# KickerBoard-new-small.net
KiCad netlist of a schematic drawn in EAGLE
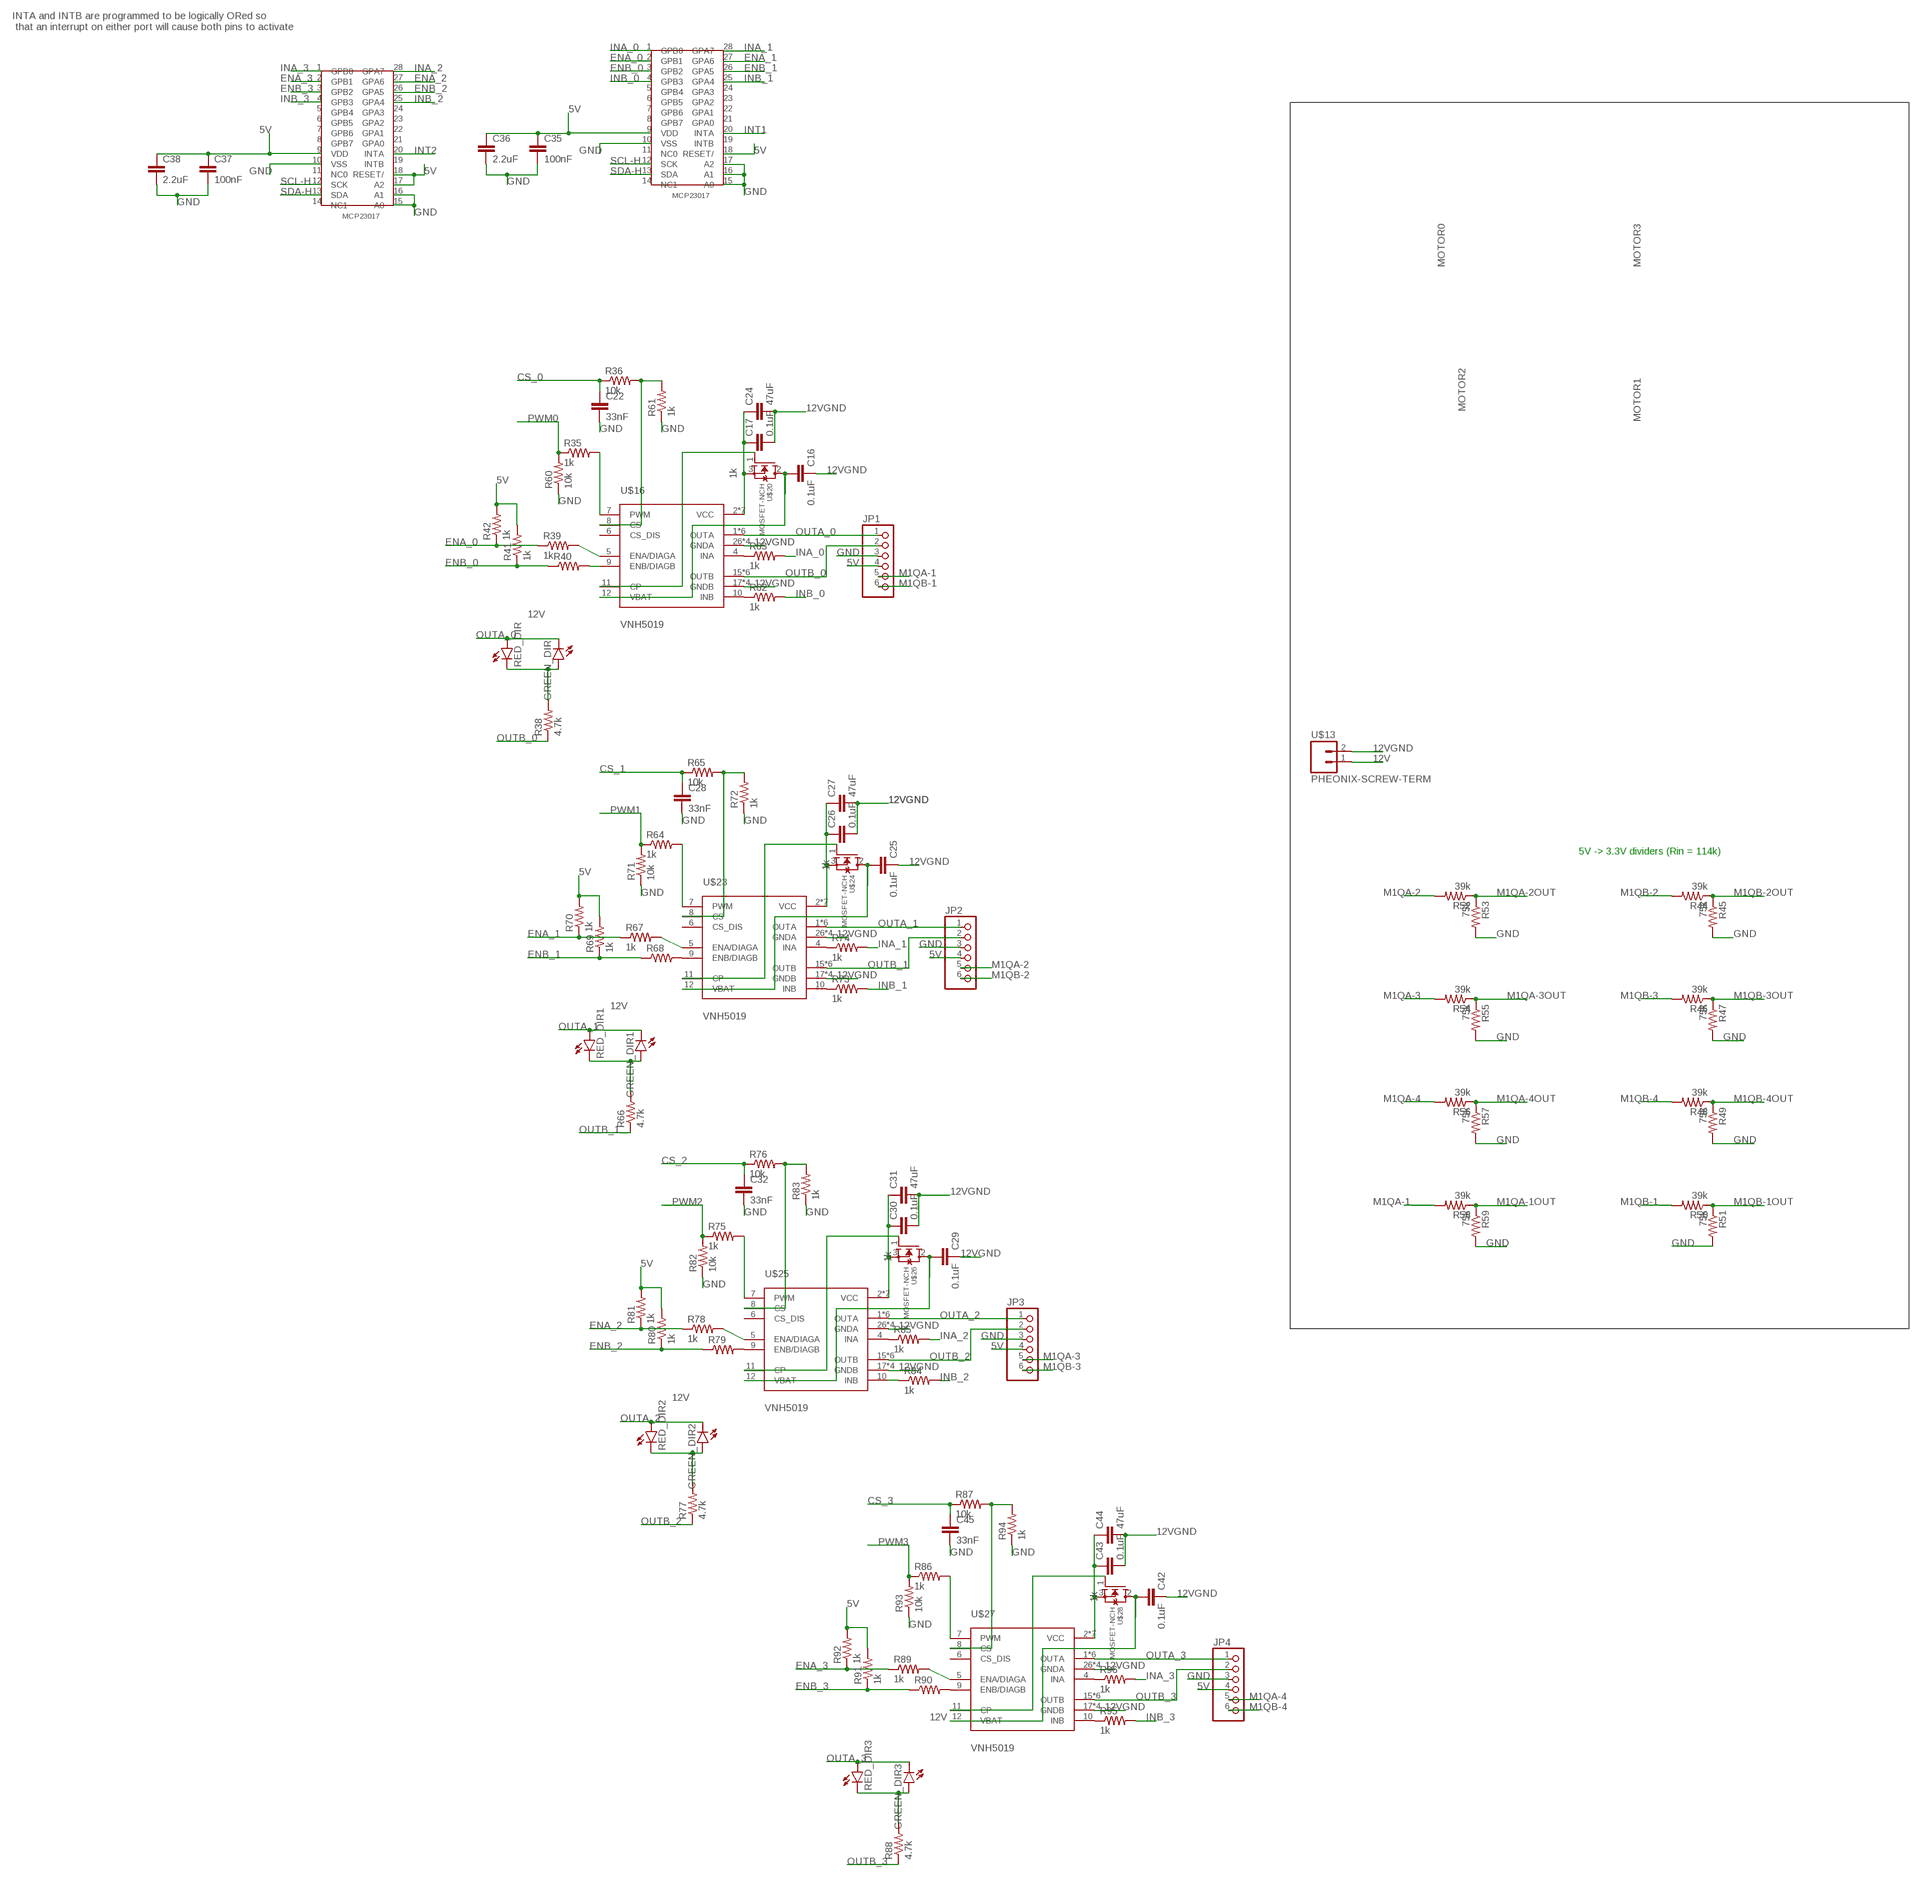
[diagram p0: schematic, sheet 1, part 1 of 2]
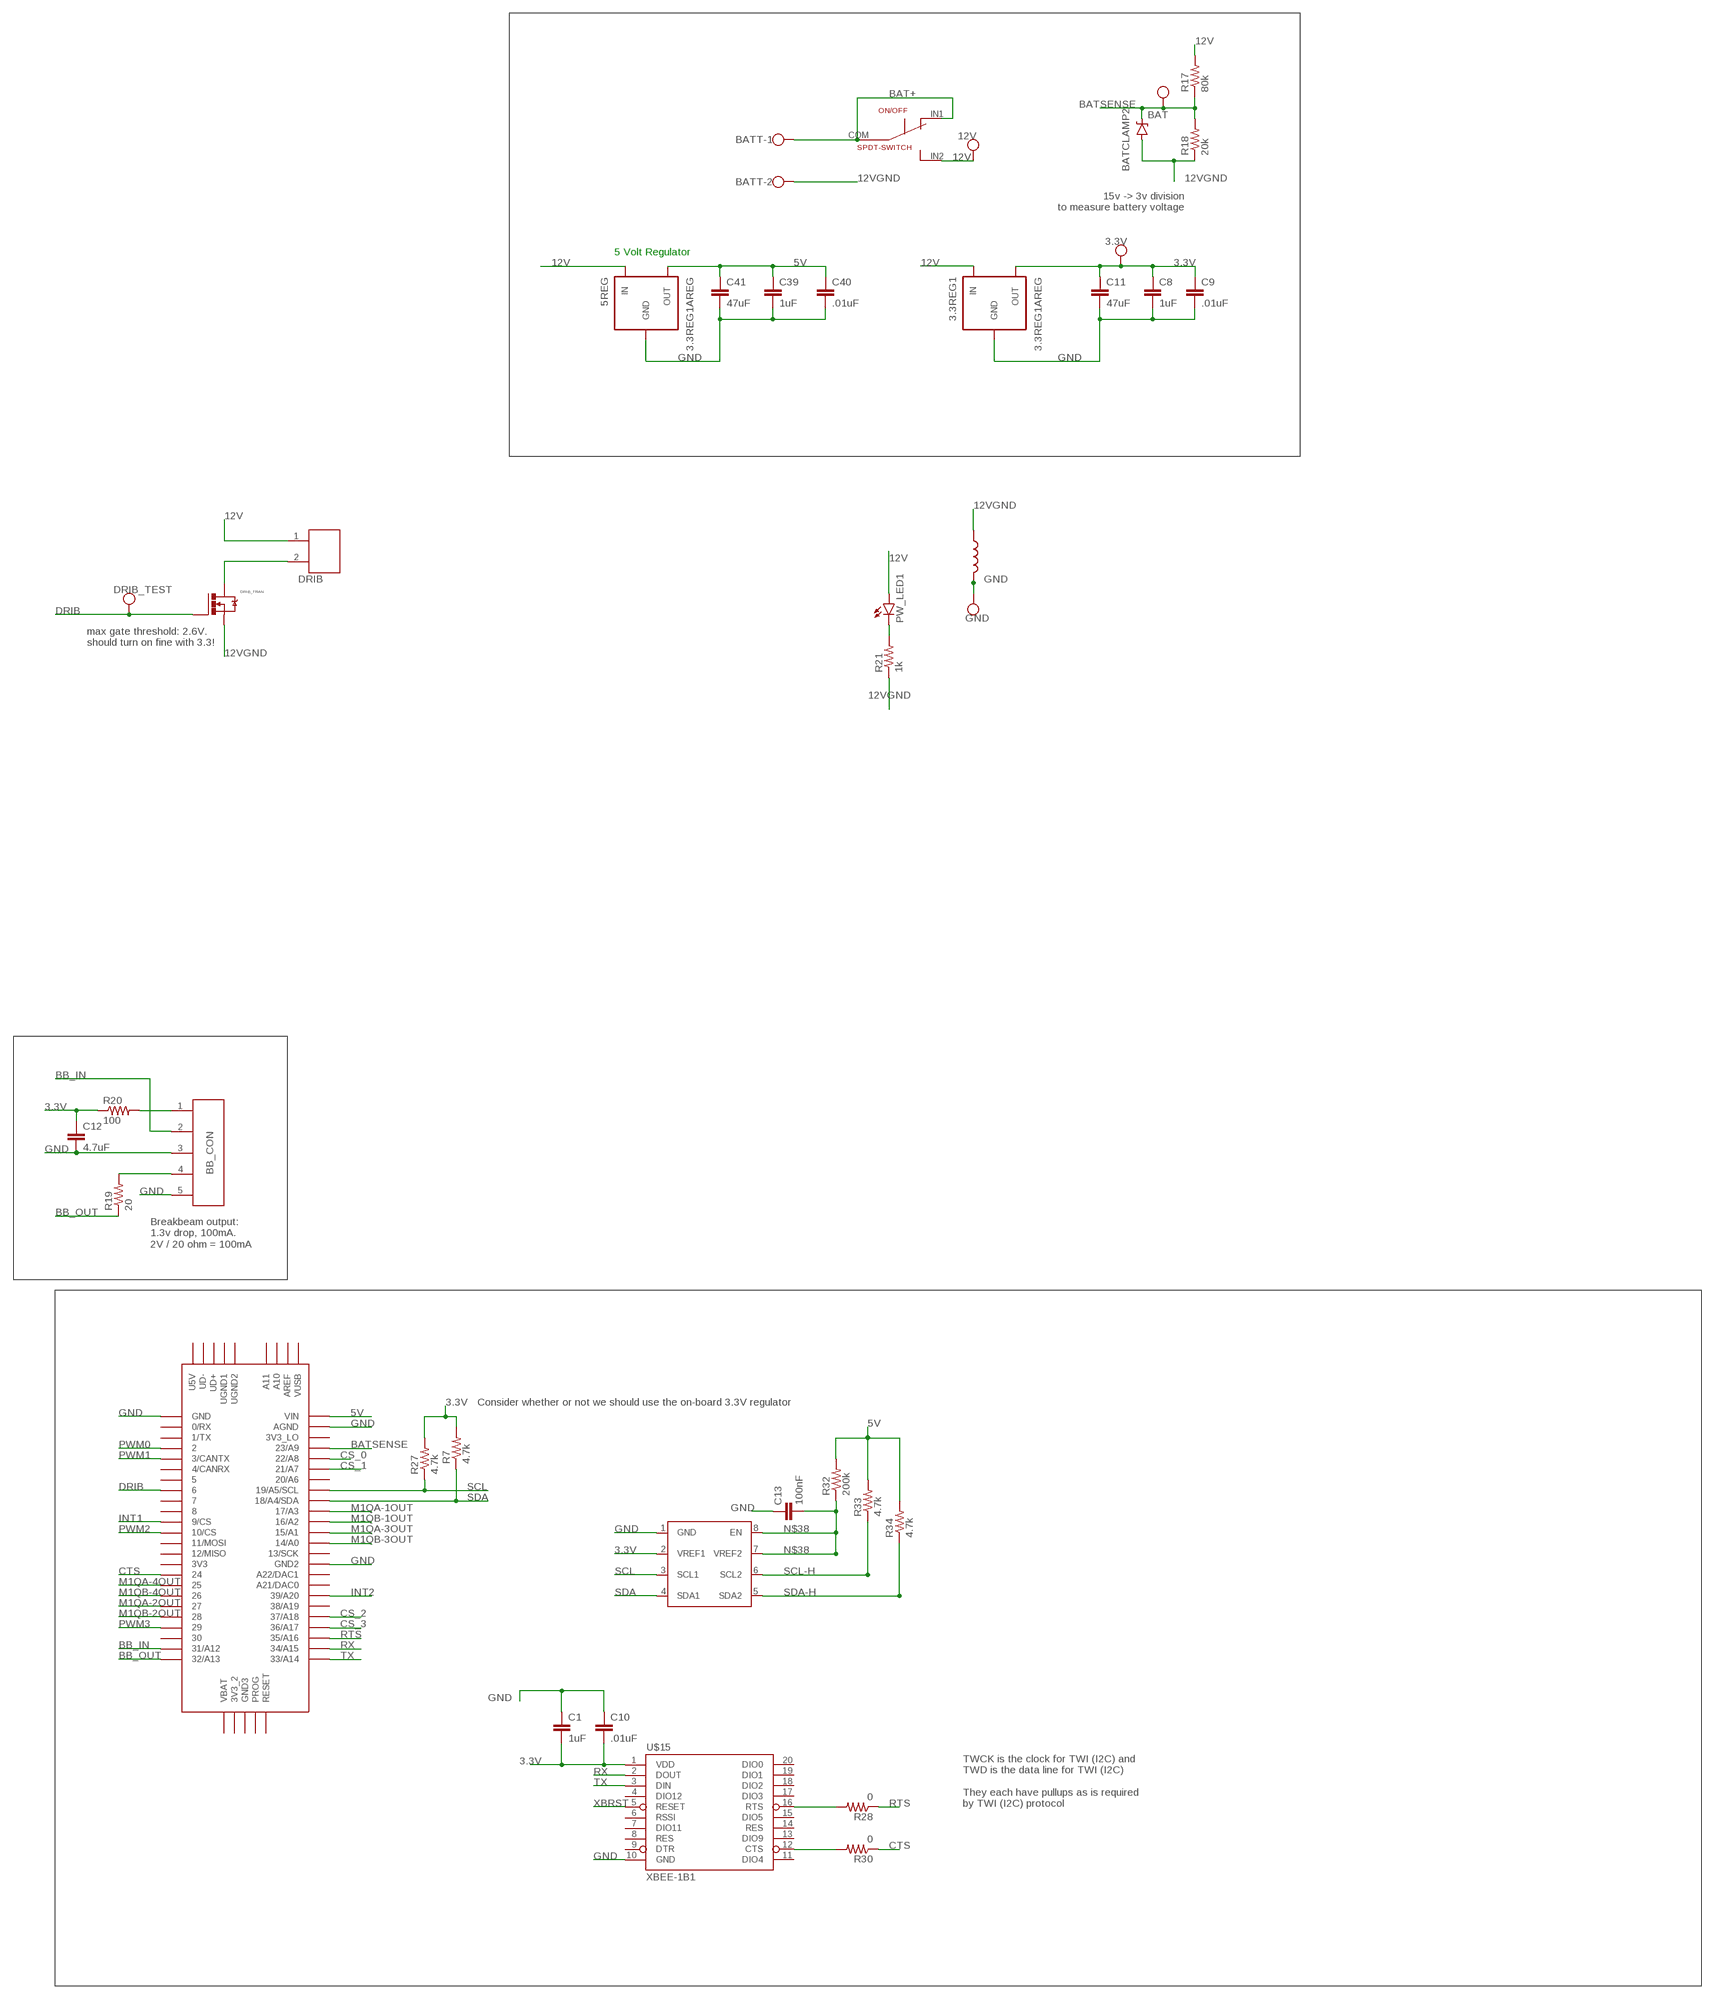
[diagram p1: schematic, sheet 1, part 2 of 2]

(export (version "E")
  (design (tool "Eeschema 10.0.6"))
  (components
    (comp (ref "3.3REG1")
      (value "3.3REG1AREG")
      (footprint "eagle-import:DPAK")
      (libsource (lib "eagle-import") (part "3.3REG1AREG"))
    )
    (comp (ref "3.3V")
      (value "TEST_PT")
      (footprint "eagle-import:TESTING_PT")
      (libsource (lib "eagle-import") (part "TEST_PT"))
    )
    (comp (ref "5REG")
      (value "3.3REG1AREG")
      (footprint "eagle-import:DPAK")
      (libsource (lib "eagle-import") (part "3.3REG1AREG"))
    )
    (comp (ref "12V")
      (value "TEST_PT")
      (footprint "eagle-import:TESTING_PT")
      (libsource (lib "eagle-import") (part "TEST_PT"))
    )
    (comp (ref "BAT")
      (value "TEST_PT")
      (footprint "eagle-import:TESTING_PT")
      (libsource (lib "eagle-import") (part "TEST_PT"))
    )
    (comp (ref "BATCLAMP2")
      (value "DIODE-ZENERDO214AC")
      (footprint "eagle-import:DO214AC")
      (libsource (lib "eagle-import") (part "DIODE-ZENERDO214AC"))
    )
    (comp (ref "BATT")
      (value "W237-102")
      (footprint "eagle-import:W237-102")
      (fields (field (name "MPN") "237-102"))
      (libsource (lib "eagle-import") (part "W237-102"))
    )
    (comp (ref "BB_CON")
      (value "JST-5")
      (footprint "eagle-import:JST-5-2MM")
      (libsource (lib "eagle-import") (part "JST-5"))
    )
    (comp (ref "C1")
      (value "1uF")
      (footprint "eagle-import:1206")
      (libsource (lib "eagle-import") (part "CAP1206"))
    )
    (comp (ref "C8")
      (value "1uF")
      (footprint "eagle-import:0805")
      (libsource (lib "eagle-import") (part "CAP0805"))
    )
    (comp (ref "C9")
      (value ".01uF")
      (footprint "eagle-import:0805")
      (libsource (lib "eagle-import") (part "CAP0805"))
    )
    (comp (ref "C10")
      (value ".01uF")
      (footprint "eagle-import:1206")
      (libsource (lib "eagle-import") (part "CAP1206"))
    )
    (comp (ref "C11")
      (value "47uF")
      (footprint "eagle-import:1206")
      (libsource (lib "eagle-import") (part "CAP1206"))
    )
    (comp (ref "C12")
      (value "4.7uF")
      (footprint "eagle-import:0805")
      (libsource (lib "eagle-import") (part "CAP0805"))
    )
    (comp (ref "C13")
      (value "100nF")
      (footprint "eagle-import:0805")
      (libsource (lib "eagle-import") (part "CAP0805"))
    )
    (comp (ref "C16")
      (value "0.1uF")
      (footprint "eagle-import:0805")
      (libsource (lib "eagle-import") (part "CAP0805"))
    )
    (comp (ref "C17")
      (value "0.1uF")
      (footprint "eagle-import:0805")
      (libsource (lib "eagle-import") (part "CAP0805"))
    )
    (comp (ref "C22")
      (value "33nF")
      (footprint "eagle-import:0805")
      (libsource (lib "eagle-import") (part "CAP0805"))
    )
    (comp (ref "C24")
      (value "47uF")
      (footprint "eagle-import:1206")
      (libsource (lib "eagle-import") (part "CAP1206"))
    )
    (comp (ref "C25")
      (value "0.1uF")
      (footprint "eagle-import:0805")
      (libsource (lib "eagle-import") (part "CAP0805"))
    )
    (comp (ref "C26")
      (value "0.1uF")
      (footprint "eagle-import:0805")
      (libsource (lib "eagle-import") (part "CAP0805"))
    )
    (comp (ref "C27")
      (value "47uF")
      (footprint "eagle-import:1206")
      (libsource (lib "eagle-import") (part "CAP1206"))
    )
    (comp (ref "C28")
      (value "33nF")
      (footprint "eagle-import:0805")
      (libsource (lib "eagle-import") (part "CAP0805"))
    )
    (comp (ref "C29")
      (value "0.1uF")
      (footprint "eagle-import:0805")
      (libsource (lib "eagle-import") (part "CAP0805"))
    )
    (comp (ref "C30")
      (value "0.1uF")
      (footprint "eagle-import:0805")
      (libsource (lib "eagle-import") (part "CAP0805"))
    )
    (comp (ref "C31")
      (value "47uF")
      (footprint "eagle-import:1206")
      (libsource (lib "eagle-import") (part "CAP1206"))
    )
    (comp (ref "C32")
      (value "33nF")
      (footprint "eagle-import:0805")
      (libsource (lib "eagle-import") (part "CAP0805"))
    )
    (comp (ref "C35")
      (value "100nF")
      (footprint "eagle-import:0805")
      (libsource (lib "eagle-import") (part "CAP0805"))
    )
    (comp (ref "C36")
      (value "2.2uF")
      (footprint "eagle-import:0805")
      (libsource (lib "eagle-import") (part "CAP0805"))
    )
    (comp (ref "C37")
      (value "100nF")
      (footprint "eagle-import:0805")
      (libsource (lib "eagle-import") (part "CAP0805"))
    )
    (comp (ref "C38")
      (value "2.2uF")
      (footprint "eagle-import:0805")
      (libsource (lib "eagle-import") (part "CAP0805"))
    )
    (comp (ref "C39")
      (value "1uF")
      (footprint "eagle-import:0805")
      (libsource (lib "eagle-import") (part "CAP0805"))
    )
    (comp (ref "C40")
      (value ".01uF")
      (footprint "eagle-import:0805")
      (libsource (lib "eagle-import") (part "CAP0805"))
    )
    (comp (ref "C41")
      (value "47uF")
      (footprint "eagle-import:1206")
      (libsource (lib "eagle-import") (part "CAP1206"))
    )
    (comp (ref "C42")
      (value "0.1uF")
      (footprint "eagle-import:0805")
      (libsource (lib "eagle-import") (part "CAP0805"))
    )
    (comp (ref "C43")
      (value "0.1uF")
      (footprint "eagle-import:0805")
      (libsource (lib "eagle-import") (part "CAP0805"))
    )
    (comp (ref "C44")
      (value "47uF")
      (footprint "eagle-import:1206")
      (libsource (lib "eagle-import") (part "CAP1206"))
    )
    (comp (ref "C45")
      (value "33nF")
      (footprint "eagle-import:0805")
      (libsource (lib "eagle-import") (part "CAP0805"))
    )
    (comp (ref "DRIB")
      (value "JST-22MM")
      (footprint "eagle-import:JST-2-2MM")
      (libsource (lib "eagle-import") (part "JST-22MM"))
    )
    (comp (ref "DRIB_TEST")
      (value "TEST_PT")
      (footprint "eagle-import:TESTING_PT")
      (libsource (lib "eagle-import") (part "TEST_PT"))
    )
    (comp (ref "DRIB_TRAN")
      (value "N-MOSFETDPAK")
      (footprint "eagle-import:DPAK")
      (libsource (lib "eagle-import") (part "N-MOSFETDPAK"))
    )
    (comp (ref "GND")
      (value "TEST_PT")
      (footprint "eagle-import:TESTING_PT")
      (libsource (lib "eagle-import") (part "TEST_PT"))
    )
    (comp (ref "GREEN_DIR")
      (value "LED1206")
      (footprint "eagle-import:LED-1206")
      (libsource (lib "eagle-import") (part "LED1206"))
    )
    (comp (ref "GREEN_DIR1")
      (value "LED1206")
      (footprint "eagle-import:LED-1206")
      (libsource (lib "eagle-import") (part "LED1206"))
    )
    (comp (ref "GREEN_DIR2")
      (value "LED1206")
      (footprint "eagle-import:LED-1206")
      (libsource (lib "eagle-import") (part "LED1206"))
    )
    (comp (ref "GREEN_DIR3")
      (value "LED1206")
      (footprint "eagle-import:LED-1206")
      (libsource (lib "eagle-import") (part "LED1206"))
    )
    (comp (ref "JP1")
      (value "PINHD-1X6")
      (footprint "eagle-import:1X06")
      (libsource (lib "eagle-import") (part "PINHD-1X6"))
    )
    (comp (ref "JP2")
      (value "PINHD-1X6")
      (footprint "eagle-import:1X06")
      (libsource (lib "eagle-import") (part "PINHD-1X6"))
    )
    (comp (ref "JP3")
      (value "PINHD-1X6")
      (footprint "eagle-import:1X06")
      (libsource (lib "eagle-import") (part "PINHD-1X6"))
    )
    (comp (ref "JP4")
      (value "PINHD-1X6")
      (footprint "eagle-import:1X06")
      (libsource (lib "eagle-import") (part "PINHD-1X6"))
    )
    (comp (ref "ON/OFF")
      (value "SPDT-SWITCH")
      (footprint "eagle-import:CK_SWITCH")
      (libsource (lib "eagle-import") (part "SPDT-SWITCH"))
    )
    (comp (ref "PW_LED1")
      (value "LED1206")
      (footprint "eagle-import:LED-1206")
      (libsource (lib "eagle-import") (part "LED1206"))
    )
    (comp (ref "R7")
      (value "4.7k")
      (footprint "eagle-import:0805")
      (libsource (lib "eagle-import") (part "SparkFun-Resistors_RESISTOR0805-RES"))
    )
    (comp (ref "R17")
      (value "80k")
      (footprint "eagle-import:0805")
      (libsource (lib "eagle-import") (part "RESISTOR0805-RES"))
    )
    (comp (ref "R18")
      (value "20k")
      (footprint "eagle-import:0805")
      (libsource (lib "eagle-import") (part "RESISTOR0805-RES"))
    )
    (comp (ref "R19")
      (value "20")
      (footprint "eagle-import:0805")
      (libsource (lib "eagle-import") (part "RESISTOR0805-RES"))
    )
    (comp (ref "R20")
      (value "100")
      (footprint "eagle-import:0805")
      (libsource (lib "eagle-import") (part "RESISTOR0805-RES"))
    )
    (comp (ref "R21")
      (value "1k")
      (footprint "eagle-import:0805")
      (libsource (lib "eagle-import") (part "RESISTOR0805-RES"))
    )
    (comp (ref "R27")
      (value "4.7k")
      (footprint "eagle-import:0805")
      (libsource (lib "eagle-import") (part "SparkFun-Resistors_RESISTOR0805-RES"))
    )
    (comp (ref "R28")
      (value "0")
      (footprint "eagle-import:0805")
      (libsource (lib "eagle-import") (part "SparkFun-Resistors_RESISTOR0805-RES"))
    )
    (comp (ref "R30")
      (value "0")
      (footprint "eagle-import:0805")
      (libsource (lib "eagle-import") (part "SparkFun-Resistors_RESISTOR0805-RES"))
    )
    (comp (ref "R32")
      (value "200k")
      (footprint "eagle-import:0805")
      (libsource (lib "eagle-import") (part "SparkFun-Resistors_RESISTOR0805-RES"))
    )
    (comp (ref "R33")
      (value "4.7k")
      (footprint "eagle-import:0805")
      (libsource (lib "eagle-import") (part "SparkFun-Resistors_RESISTOR0805-RES"))
    )
    (comp (ref "R34")
      (value "4.7k")
      (footprint "eagle-import:0805")
      (libsource (lib "eagle-import") (part "SparkFun-Resistors_RESISTOR0805-RES"))
    )
    (comp (ref "R35")
      (value "1k")
      (footprint "eagle-import:0805")
      (libsource (lib "eagle-import") (part "RESISTOR0805-RES"))
    )
    (comp (ref "R36")
      (value "10k")
      (footprint "eagle-import:0805")
      (libsource (lib "eagle-import") (part "RESISTOR0805-RES"))
    )
    (comp (ref "R38")
      (value "4.7k")
      (footprint "eagle-import:0805")
      (libsource (lib "eagle-import") (part "RESISTOR0805-RES"))
    )
    (comp (ref "R39")
      (value "1k")
      (footprint "eagle-import:0805")
      (libsource (lib "eagle-import") (part "RESISTOR0805-RES"))
    )
    (comp (ref "R40")
      (value "1k")
      (footprint "eagle-import:0805")
      (libsource (lib "eagle-import") (part "RESISTOR0805-RES"))
    )
    (comp (ref "R41")
      (value "1k")
      (footprint "eagle-import:0805")
      (libsource (lib "eagle-import") (part "RESISTOR0805-RES"))
    )
    (comp (ref "R42")
      (value "1k")
      (footprint "eagle-import:0805")
      (libsource (lib "eagle-import") (part "RESISTOR0805-RES"))
    )
    (comp (ref "R44")
      (value "39k")
      (footprint "eagle-import:0805")
      (libsource (lib "eagle-import") (part "RESISTOR0805-RES"))
    )
    (comp (ref "R45")
      (value "75k")
      (footprint "eagle-import:0805")
      (libsource (lib "eagle-import") (part "RESISTOR0805-RES"))
    )
    (comp (ref "R46")
      (value "39k")
      (footprint "eagle-import:0805")
      (libsource (lib "eagle-import") (part "RESISTOR0805-RES"))
    )
    (comp (ref "R47")
      (value "75k")
      (footprint "eagle-import:0805")
      (libsource (lib "eagle-import") (part "RESISTOR0805-RES"))
    )
    (comp (ref "R48")
      (value "39k")
      (footprint "eagle-import:0805")
      (libsource (lib "eagle-import") (part "RESISTOR0805-RES"))
    )
    (comp (ref "R49")
      (value "75k")
      (footprint "eagle-import:0805")
      (libsource (lib "eagle-import") (part "RESISTOR0805-RES"))
    )
    (comp (ref "R50")
      (value "39k")
      (footprint "eagle-import:0805")
      (libsource (lib "eagle-import") (part "RESISTOR0805-RES"))
    )
    (comp (ref "R51")
      (value "75k")
      (footprint "eagle-import:0805")
      (libsource (lib "eagle-import") (part "RESISTOR0805-RES"))
    )
    (comp (ref "R52")
      (value "39k")
      (footprint "eagle-import:0805")
      (libsource (lib "eagle-import") (part "RESISTOR0805-RES"))
    )
    (comp (ref "R53")
      (value "75k")
      (footprint "eagle-import:0805")
      (libsource (lib "eagle-import") (part "RESISTOR0805-RES"))
    )
    (comp (ref "R54")
      (value "39k")
      (footprint "eagle-import:0805")
      (libsource (lib "eagle-import") (part "RESISTOR0805-RES"))
    )
    (comp (ref "R55")
      (value "75k")
      (footprint "eagle-import:0805")
      (libsource (lib "eagle-import") (part "RESISTOR0805-RES"))
    )
    (comp (ref "R56")
      (value "39k")
      (footprint "eagle-import:0805")
      (libsource (lib "eagle-import") (part "RESISTOR0805-RES"))
    )
    (comp (ref "R57")
      (value "75k")
      (footprint "eagle-import:0805")
      (libsource (lib "eagle-import") (part "RESISTOR0805-RES"))
    )
    (comp (ref "R58")
      (value "39k")
      (footprint "eagle-import:0805")
      (libsource (lib "eagle-import") (part "RESISTOR0805-RES"))
    )
    (comp (ref "R59")
      (value "75k")
      (footprint "eagle-import:0805")
      (libsource (lib "eagle-import") (part "RESISTOR0805-RES"))
    )
    (comp (ref "R60")
      (value "10k")
      (footprint "eagle-import:0805")
      (libsource (lib "eagle-import") (part "RESISTOR0805-RES"))
    )
    (comp (ref "R61")
      (value "1k")
      (footprint "eagle-import:0805")
      (libsource (lib "eagle-import") (part "RESISTOR0805-RES"))
    )
    (comp (ref "R62")
      (value "1k")
      (footprint "eagle-import:0805")
      (libsource (lib "eagle-import") (part "RESISTOR0805-RES"))
    )
    (comp (ref "R63")
      (value "1k")
      (footprint "eagle-import:0805")
      (libsource (lib "eagle-import") (part "RESISTOR0805-RES"))
    )
    (comp (ref "R64")
      (value "1k")
      (footprint "eagle-import:0805")
      (libsource (lib "eagle-import") (part "RESISTOR0805-RES"))
    )
    (comp (ref "R65")
      (value "10k")
      (footprint "eagle-import:0805")
      (libsource (lib "eagle-import") (part "RESISTOR0805-RES"))
    )
    (comp (ref "R66")
      (value "4.7k")
      (footprint "eagle-import:0805")
      (libsource (lib "eagle-import") (part "RESISTOR0805-RES"))
    )
    (comp (ref "R67")
      (value "1k")
      (footprint "eagle-import:0805")
      (libsource (lib "eagle-import") (part "RESISTOR0805-RES"))
    )
    (comp (ref "R68")
      (value "1k")
      (footprint "eagle-import:0805")
      (libsource (lib "eagle-import") (part "RESISTOR0805-RES"))
    )
    (comp (ref "R69")
      (value "1k")
      (footprint "eagle-import:0805")
      (libsource (lib "eagle-import") (part "RESISTOR0805-RES"))
    )
    (comp (ref "R70")
      (value "1k")
      (footprint "eagle-import:0805")
      (libsource (lib "eagle-import") (part "RESISTOR0805-RES"))
    )
    (comp (ref "R71")
      (value "10k")
      (footprint "eagle-import:0805")
      (libsource (lib "eagle-import") (part "RESISTOR0805-RES"))
    )
    (comp (ref "R72")
      (value "1k")
      (footprint "eagle-import:0805")
      (libsource (lib "eagle-import") (part "RESISTOR0805-RES"))
    )
    (comp (ref "R73")
      (value "1k")
      (footprint "eagle-import:0805")
      (libsource (lib "eagle-import") (part "RESISTOR0805-RES"))
    )
    (comp (ref "R74")
      (value "1k")
      (footprint "eagle-import:0805")
      (libsource (lib "eagle-import") (part "RESISTOR0805-RES"))
    )
    (comp (ref "R75")
      (value "1k")
      (footprint "eagle-import:0805")
      (libsource (lib "eagle-import") (part "RESISTOR0805-RES"))
    )
    (comp (ref "R76")
      (value "10k")
      (footprint "eagle-import:0805")
      (libsource (lib "eagle-import") (part "RESISTOR0805-RES"))
    )
    (comp (ref "R77")
      (value "4.7k")
      (footprint "eagle-import:0805")
      (libsource (lib "eagle-import") (part "RESISTOR0805-RES"))
    )
    (comp (ref "R78")
      (value "1k")
      (footprint "eagle-import:0805")
      (libsource (lib "eagle-import") (part "RESISTOR0805-RES"))
    )
    (comp (ref "R79")
      (value "1k")
      (footprint "eagle-import:0805")
      (libsource (lib "eagle-import") (part "RESISTOR0805-RES"))
    )
    (comp (ref "R80")
      (value "1k")
      (footprint "eagle-import:0805")
      (libsource (lib "eagle-import") (part "RESISTOR0805-RES"))
    )
    (comp (ref "R81")
      (value "1k")
      (footprint "eagle-import:0805")
      (libsource (lib "eagle-import") (part "RESISTOR0805-RES"))
    )
    (comp (ref "R82")
      (value "10k")
      (footprint "eagle-import:0805")
      (libsource (lib "eagle-import") (part "RESISTOR0805-RES"))
    )
    (comp (ref "R83")
      (value "1k")
      (footprint "eagle-import:0805")
      (libsource (lib "eagle-import") (part "RESISTOR0805-RES"))
    )
    (comp (ref "R84")
      (value "1k")
      (footprint "eagle-import:0805")
      (libsource (lib "eagle-import") (part "RESISTOR0805-RES"))
    )
    (comp (ref "R85")
      (value "1k")
      (footprint "eagle-import:0805")
      (libsource (lib "eagle-import") (part "RESISTOR0805-RES"))
    )
    (comp (ref "R86")
      (value "1k")
      (footprint "eagle-import:0805")
      (libsource (lib "eagle-import") (part "RESISTOR0805-RES"))
    )
    (comp (ref "R87")
      (value "10k")
      (footprint "eagle-import:0805")
      (libsource (lib "eagle-import") (part "RESISTOR0805-RES"))
    )
    (comp (ref "R88")
      (value "4.7k")
      (footprint "eagle-import:0805")
      (libsource (lib "eagle-import") (part "RESISTOR0805-RES"))
    )
    (comp (ref "R89")
      (value "1k")
      (footprint "eagle-import:0805")
      (libsource (lib "eagle-import") (part "RESISTOR0805-RES"))
    )
    (comp (ref "R90")
      (value "1k")
      (footprint "eagle-import:0805")
      (libsource (lib "eagle-import") (part "RESISTOR0805-RES"))
    )
    (comp (ref "R91")
      (value "1k")
      (footprint "eagle-import:0805")
      (libsource (lib "eagle-import") (part "RESISTOR0805-RES"))
    )
    (comp (ref "R92")
      (value "1k")
      (footprint "eagle-import:0805")
      (libsource (lib "eagle-import") (part "RESISTOR0805-RES"))
    )
    (comp (ref "R93")
      (value "10k")
      (footprint "eagle-import:0805")
      (libsource (lib "eagle-import") (part "RESISTOR0805-RES"))
    )
    (comp (ref "R94")
      (value "1k")
      (footprint "eagle-import:0805")
      (libsource (lib "eagle-import") (part "RESISTOR0805-RES"))
    )
    (comp (ref "R95")
      (value "1k")
      (footprint "eagle-import:0805")
      (libsource (lib "eagle-import") (part "RESISTOR0805-RES"))
    )
    (comp (ref "R96")
      (value "1k")
      (footprint "eagle-import:0805")
      (libsource (lib "eagle-import") (part "RESISTOR0805-RES"))
    )
    (comp (ref "RED_DIR")
      (value "LED1206")
      (footprint "eagle-import:LED-1206")
      (libsource (lib "eagle-import") (part "LED1206"))
    )
    (comp (ref "RED_DIR1")
      (value "LED1206")
      (footprint "eagle-import:LED-1206")
      (libsource (lib "eagle-import") (part "LED1206"))
    )
    (comp (ref "RED_DIR2")
      (value "LED1206")
      (footprint "eagle-import:LED-1206")
      (libsource (lib "eagle-import") (part "LED1206"))
    )
    (comp (ref "RED_DIR3")
      (value "LED1206")
      (footprint "eagle-import:LED-1206")
      (libsource (lib "eagle-import") (part "LED1206"))
    )
    (comp (ref "U$8")
      (value "PCA9306")
      (footprint "eagle-import:SOIC8")
      (libsource (lib "eagle-import") (part "PCA9306"))
    )
    (comp (ref "U$13")
      (value "PHEONIX-SCREW-TERM")
      (footprint "eagle-import:1X02-PHEONIX")
      (libsource (lib "eagle-import") (part "PHEONIX-SCREW-TERM"))
    )
    (comp (ref "U$14")
      (value "TEENSY_3.5/3.6")
      (footprint "eagle-import:TEENSY_3.5_3.6")
      (libsource (lib "eagle-import") (part "TEENSY_3.5/3.6"))
    )
    (comp (ref "U$15")
      (value "XBEE-1B1")
      (footprint "eagle-import:XBEE-1")
      (libsource (lib "eagle-import") (part "XBEE-1B1"))
    )
    (comp (ref "U$16")
      (value "VNH5019")
      (footprint "eagle-import:MULTIPOWERSO-30")
      (libsource (lib "eagle-import") (part "VNH5019"))
    )
    (comp (ref "U$17")
      (value "IO-EXPANDER")
      (footprint "eagle-import:SSOP")
      (libsource (lib "eagle-import") (part "IO-EXPANDER"))
    )
    (comp (ref "U$19")
      (value "INDUCTOR")
      (footprint "eagle-import:0805")
      (libsource (lib "eagle-import") (part "INDUCTOR"))
    )
    (comp (ref "U$20")
      (value "MOSFET-NCH")
      (footprint "eagle-import:TO252-3")
      (libsource (lib "eagle-import") (part "MOSFET-NCH"))
    )
    (comp (ref "U$21")
      (value "IO-EXPANDER")
      (footprint "eagle-import:SSOP")
      (libsource (lib "eagle-import") (part "IO-EXPANDER"))
    )
    (comp (ref "U$23")
      (value "VNH5019")
      (footprint "eagle-import:MULTIPOWERSO-30")
      (libsource (lib "eagle-import") (part "VNH5019"))
    )
    (comp (ref "U$24")
      (value "MOSFET-NCH")
      (footprint "eagle-import:TO252-3")
      (libsource (lib "eagle-import") (part "MOSFET-NCH"))
    )
    (comp (ref "U$25")
      (value "VNH5019")
      (footprint "eagle-import:MULTIPOWERSO-30")
      (libsource (lib "eagle-import") (part "VNH5019"))
    )
    (comp (ref "U$26")
      (value "MOSFET-NCH")
      (footprint "eagle-import:TO252-3")
      (libsource (lib "eagle-import") (part "MOSFET-NCH"))
    )
    (comp (ref "U$27")
      (value "VNH5019")
      (footprint "eagle-import:MULTIPOWERSO-30")
      (libsource (lib "eagle-import") (part "VNH5019"))
    )
    (comp (ref "U$28")
      (value "MOSFET-NCH")
      (footprint "eagle-import:TO252-3")
      (libsource (lib "eagle-import") (part "MOSFET-NCH"))
    )
  )
  (nets
    (net (code "1") (name "/3.3V") (class "Default")
      (node (ref "3.3REG1") (pin "SOURCE") (pinfunction "OUT_SOURCE") (pintype "bidirectional"))
      (node (ref "3.3V") (pin "P$1") (pinfunction "P$1_P$1") (pintype "bidirectional"))
      (node (ref "C1") (pin "2") (pinfunction "2_2") (pintype "passive"))
      (node (ref "C10") (pin "2") (pinfunction "2_2") (pintype "passive"))
      (node (ref "C11") (pin "1") (pinfunction "1_1") (pintype "passive"))
      (node (ref "C12") (pin "1") (pinfunction "1_1") (pintype "passive"))
      (node (ref "C8") (pin "1") (pinfunction "1_1") (pintype "passive"))
      (node (ref "C9") (pin "1") (pinfunction "1_1") (pintype "passive"))
      (node (ref "R20") (pin "1") (pinfunction "1_1") (pintype "passive"))
      (node (ref "R27") (pin "2") (pinfunction "2_2") (pintype "passive"))
      (node (ref "R7") (pin "2") (pinfunction "2_2") (pintype "passive"))
      (node (ref "U$15") (pin "1") (pinfunction "VDD_1") (pintype "power_in"))
      (node (ref "U$8") (pin "2") (pinfunction "VREF1_2") (pintype "bidirectional"))
    )
    (net (code "2") (name "/5V") (class "Default")
      (node (ref "5REG") (pin "SOURCE") (pinfunction "OUT_SOURCE") (pintype "bidirectional"))
      (node (ref "C35") (pin "1") (pinfunction "1_1") (pintype "passive"))
      (node (ref "C36") (pin "1") (pinfunction "1_1") (pintype "passive"))
      (node (ref "C37") (pin "1") (pinfunction "1_1") (pintype "passive"))
      (node (ref "C38") (pin "1") (pinfunction "1_1") (pintype "passive"))
      (node (ref "C39") (pin "1") (pinfunction "1_1") (pintype "passive"))
      (node (ref "C40") (pin "1") (pinfunction "1_1") (pintype "passive"))
      (node (ref "C41") (pin "1") (pinfunction "1_1") (pintype "passive"))
      (node (ref "JP1") (pin "4") (pinfunction "4_4") (pintype "passive"))
      (node (ref "JP2") (pin "4") (pinfunction "4_4") (pintype "passive"))
      (node (ref "JP3") (pin "4") (pinfunction "4_4") (pintype "passive"))
      (node (ref "JP4") (pin "4") (pinfunction "4_4") (pintype "passive"))
      (node (ref "R32") (pin "2") (pinfunction "2_2") (pintype "passive"))
      (node (ref "R33") (pin "2") (pinfunction "2_2") (pintype "passive"))
      (node (ref "R34") (pin "2") (pinfunction "2_2") (pintype "passive"))
      (node (ref "R41") (pin "2") (pinfunction "2_2") (pintype "passive"))
      (node (ref "R42") (pin "2") (pinfunction "2_2") (pintype "passive"))
      (node (ref "R69") (pin "2") (pinfunction "2_2") (pintype "passive"))
      (node (ref "R70") (pin "2") (pinfunction "2_2") (pintype "passive"))
      (node (ref "R80") (pin "2") (pinfunction "2_2") (pintype "passive"))
      (node (ref "R81") (pin "2") (pinfunction "2_2") (pintype "passive"))
      (node (ref "R91") (pin "2") (pinfunction "2_2") (pintype "passive"))
      (node (ref "R92") (pin "2") (pinfunction "2_2") (pintype "passive"))
      (node (ref "U$14") (pin "VIN") (pinfunction "VIN_VIN") (pintype "bidirectional"))
      (node (ref "U$17") (pin "18") (pinfunction "RESET/_18") (pintype "bidirectional"))
      (node (ref "U$17") (pin "9") (pinfunction "VDD_9") (pintype "bidirectional"))
      (node (ref "U$21") (pin "17") (pinfunction "A2_17") (pintype "bidirectional"))
      (node (ref "U$21") (pin "18") (pinfunction "RESET/_18") (pintype "bidirectional"))
      (node (ref "U$21") (pin "9") (pinfunction "VDD_9") (pintype "bidirectional"))
    )
    (net (code "3") (name "/12V") (class "Default")
      (node (ref "12V") (pin "P$1") (pinfunction "P$1_P$1") (pintype "bidirectional"))
      (node (ref "3.3REG1") (pin "GATE") (pinfunction "IN_GATE") (pintype "input"))
      (node (ref "5REG") (pin "GATE") (pinfunction "IN_GATE") (pintype "input"))
      (node (ref "C16") (pin "1") (pinfunction "1_1") (pintype "passive"))
      (node (ref "C25") (pin "1") (pinfunction "1_1") (pintype "passive"))
      (node (ref "C29") (pin "1") (pinfunction "1_1") (pintype "passive"))
      (node (ref "C42") (pin "1") (pinfunction "1_1") (pintype "passive"))
      (node (ref "DRIB") (pin "1") (pinfunction "P$1_1") (pintype "bidirectional"))
      (node (ref "ON/OFF") (pin "IN2") (pinfunction "P2_IN2") (pintype "bidirectional"))
      (node (ref "PW_LED1") (pin "A") (pinfunction "A_A") (pintype "passive"))
      (node (ref "R17") (pin "2") (pinfunction "2_2") (pintype "passive"))
      (node (ref "U$13") (pin "1") (pinfunction "1_1") (pintype "passive"))
      (node (ref "U$16") (pin "12") (pinfunction "VBAT_12") (pintype "bidirectional"))
      (node (ref "U$20") (pin "2") (pinfunction "D_2") (pintype "bidirectional"))
      (node (ref "U$23") (pin "12") (pinfunction "VBAT_12") (pintype "bidirectional"))
      (node (ref "U$24") (pin "2") (pinfunction "D_2") (pintype "bidirectional"))
      (node (ref "U$25") (pin "12") (pinfunction "VBAT_12") (pintype "bidirectional"))
      (node (ref "U$26") (pin "2") (pinfunction "D_2") (pintype "bidirectional"))
      (node (ref "U$27") (pin "12") (pinfunction "VBAT_12") (pintype "bidirectional"))
      (node (ref "U$28") (pin "2") (pinfunction "D_2") (pintype "bidirectional"))
    )
    (net (code "4") (name "/12VGND") (class "Default")
      (node (ref "BATCLAMP2") (pin "A") (pinfunction "A_A") (pintype "passive"))
      (node (ref "BATT") (pin "2") (pinfunction "KL_2") (pintype "passive"))
      (node (ref "C16") (pin "2") (pinfunction "2_2") (pintype "passive"))
      (node (ref "C17") (pin "2") (pinfunction "2_2") (pintype "passive"))
      (node (ref "C24") (pin "2") (pinfunction "2_2") (pintype "passive"))
      (node (ref "C25") (pin "2") (pinfunction "2_2") (pintype "passive"))
      (node (ref "C26") (pin "2") (pinfunction "2_2") (pintype "passive"))
      (node (ref "C27") (pin "2") (pinfunction "2_2") (pintype "passive"))
      (node (ref "C29") (pin "2") (pinfunction "2_2") (pintype "passive"))
      (node (ref "C30") (pin "2") (pinfunction "2_2") (pintype "passive"))
      (node (ref "C31") (pin "2") (pinfunction "2_2") (pintype "passive"))
      (node (ref "C42") (pin "2") (pinfunction "2_2") (pintype "passive"))
      (node (ref "C43") (pin "2") (pinfunction "2_2") (pintype "passive"))
      (node (ref "C44") (pin "2") (pinfunction "2_2") (pintype "passive"))
      (node (ref "DRIB_TRAN") (pin "SOURCE") (pinfunction "S_SOURCE") (pintype "bidirectional"))
      (node (ref "R18") (pin "1") (pinfunction "1_1") (pintype "passive"))
      (node (ref "R21") (pin "1") (pinfunction "1_1") (pintype "passive"))
      (node (ref "U$13") (pin "2") (pinfunction "2_2") (pintype "passive"))
      (node (ref "U$16") (pin "17") (pinfunction "GNDB_17") (pintype "bidirectional"))
      (node (ref "U$16") (pin "18") (pinfunction "GNDB_18") (pintype "bidirectional"))
      (node (ref "U$16") (pin "19") (pinfunction "GNDB_19") (pintype "bidirectional"))
      (node (ref "U$16") (pin "20") (pinfunction "GNDB_20") (pintype "bidirectional"))
      (node (ref "U$16") (pin "26") (pinfunction "GNDA_26") (pintype "bidirectional"))
      (node (ref "U$16") (pin "27") (pinfunction "GNDA_27") (pintype "bidirectional"))
      (node (ref "U$16") (pin "28") (pinfunction "GNDA_28") (pintype "bidirectional"))
      (node (ref "U$16") (pin "29") (pinfunction "GNDA_29") (pintype "bidirectional"))
      (node (ref "U$19") (pin "1") (pinfunction "P$1_1") (pintype "bidirectional"))
      (node (ref "U$23") (pin "17") (pinfunction "GNDB_17") (pintype "bidirectional"))
      (node (ref "U$23") (pin "18") (pinfunction "GNDB_18") (pintype "bidirectional"))
      (node (ref "U$23") (pin "19") (pinfunction "GNDB_19") (pintype "bidirectional"))
      (node (ref "U$23") (pin "20") (pinfunction "GNDB_20") (pintype "bidirectional"))
      (node (ref "U$23") (pin "26") (pinfunction "GNDA_26") (pintype "bidirectional"))
      (node (ref "U$23") (pin "27") (pinfunction "GNDA_27") (pintype "bidirectional"))
      (node (ref "U$23") (pin "28") (pinfunction "GNDA_28") (pintype "bidirectional"))
      (node (ref "U$23") (pin "29") (pinfunction "GNDA_29") (pintype "bidirectional"))
      (node (ref "U$25") (pin "17") (pinfunction "GNDB_17") (pintype "bidirectional"))
      (node (ref "U$25") (pin "18") (pinfunction "GNDB_18") (pintype "bidirectional"))
      (node (ref "U$25") (pin "19") (pinfunction "GNDB_19") (pintype "bidirectional"))
      (node (ref "U$25") (pin "20") (pinfunction "GNDB_20") (pintype "bidirectional"))
      (node (ref "U$25") (pin "26") (pinfunction "GNDA_26") (pintype "bidirectional"))
      (node (ref "U$25") (pin "27") (pinfunction "GNDA_27") (pintype "bidirectional"))
      (node (ref "U$25") (pin "28") (pinfunction "GNDA_28") (pintype "bidirectional"))
      (node (ref "U$25") (pin "29") (pinfunction "GNDA_29") (pintype "bidirectional"))
      (node (ref "U$27") (pin "17") (pinfunction "GNDB_17") (pintype "bidirectional"))
      (node (ref "U$27") (pin "18") (pinfunction "GNDB_18") (pintype "bidirectional"))
      (node (ref "U$27") (pin "19") (pinfunction "GNDB_19") (pintype "bidirectional"))
      (node (ref "U$27") (pin "20") (pinfunction "GNDB_20") (pintype "bidirectional"))
      (node (ref "U$27") (pin "26") (pinfunction "GNDA_26") (pintype "bidirectional"))
      (node (ref "U$27") (pin "27") (pinfunction "GNDA_27") (pintype "bidirectional"))
      (node (ref "U$27") (pin "28") (pinfunction "GNDA_28") (pintype "bidirectional"))
      (node (ref "U$27") (pin "29") (pinfunction "GNDA_29") (pintype "bidirectional"))
    )
    (net (code "5") (name "/BAT+") (class "Default")
      (node (ref "BATT") (pin "1") (pinfunction "KL_1") (pintype "passive"))
      (node (ref "ON/OFF") (pin "COM") (pinfunction "COM_COM") (pintype "bidirectional"))
      (node (ref "ON/OFF") (pin "IN1") (pinfunction "P1_IN1") (pintype "bidirectional"))
    )
    (net (code "6") (name "/BATSENSE") (class "Default")
      (node (ref "BAT") (pin "P$1") (pinfunction "P$1_P$1") (pintype "bidirectional"))
      (node (ref "BATCLAMP2") (pin "C") (pinfunction "C_C") (pintype "passive"))
      (node (ref "R17") (pin "1") (pinfunction "1_1") (pintype "passive"))
      (node (ref "R18") (pin "2") (pinfunction "2_2") (pintype "passive"))
      (node (ref "U$14") (pin "23/A9") (pinfunction "23/A9_23/A9") (pintype "bidirectional"))
    )
    (net (code "7") (name "/BB_IN") (class "Default")
      (node (ref "BB_CON") (pin "2") (pinfunction "P$2_2") (pintype "bidirectional"))
      (node (ref "U$14") (pin "31/A12") (pinfunction "31/A12_31/A12") (pintype "bidirectional"))
    )
    (net (code "8") (name "/BB_OUT") (class "Default")
      (node (ref "R19") (pin "1") (pinfunction "1_1") (pintype "passive"))
      (node (ref "U$14") (pin "32/A13") (pinfunction "32/A13_32/A13") (pintype "bidirectional"))
    )
    (net (code "9") (name "/CS_0") (class "Default")
      (node (ref "C22") (pin "1") (pinfunction "1_1") (pintype "passive"))
      (node (ref "R36") (pin "1") (pinfunction "1_1") (pintype "passive"))
      (node (ref "U$14") (pin "22/A8") (pinfunction "22/A8_22/A8") (pintype "bidirectional"))
    )
    (net (code "10") (name "/CS_1") (class "Default")
      (node (ref "C28") (pin "1") (pinfunction "1_1") (pintype "passive"))
      (node (ref "R65") (pin "1") (pinfunction "1_1") (pintype "passive"))
      (node (ref "U$14") (pin "21/A7") (pinfunction "21/A7_21/A7") (pintype "bidirectional"))
    )
    (net (code "11") (name "/CS_2") (class "Default")
      (node (ref "C32") (pin "1") (pinfunction "1_1") (pintype "passive"))
      (node (ref "R76") (pin "1") (pinfunction "1_1") (pintype "passive"))
      (node (ref "U$14") (pin "37/A18") (pinfunction "37/A18_37/A18") (pintype "bidirectional"))
    )
    (net (code "12") (name "/CS_3") (class "Default")
      (node (ref "C45") (pin "1") (pinfunction "1_1") (pintype "passive"))
      (node (ref "R87") (pin "1") (pinfunction "1_1") (pintype "passive"))
      (node (ref "U$14") (pin "36/A17") (pinfunction "36/A17_36/A17") (pintype "bidirectional"))
    )
    (net (code "13") (name "/CTS") (class "Default")
      (node (ref "R30") (pin "1") (pinfunction "1_1") (pintype "passive"))
      (node (ref "U$14") (pin "24") (pinfunction "24_24") (pintype "bidirectional"))
    )
    (net (code "14") (name "/DRIB") (class "Default")
      (node (ref "DRIB_TEST") (pin "P$1") (pinfunction "P$1_P$1") (pintype "bidirectional"))
      (node (ref "DRIB_TRAN") (pin "GATE") (pinfunction "G_GATE") (pintype "bidirectional"))
      (node (ref "U$14") (pin "6") (pinfunction "6_6") (pintype "bidirectional"))
    )
    (net (code "15") (name "/ENA_0") (class "Default")
      (node (ref "R39") (pin "1") (pinfunction "1_1") (pintype "passive"))
      (node (ref "R42") (pin "1") (pinfunction "1_1") (pintype "passive"))
      (node (ref "U$17") (pin "2") (pinfunction "GPB1_2") (pintype "bidirectional"))
    )
    (net (code "16") (name "/ENA_1") (class "Default")
      (node (ref "R67") (pin "1") (pinfunction "1_1") (pintype "passive"))
      (node (ref "R70") (pin "1") (pinfunction "1_1") (pintype "passive"))
      (node (ref "U$17") (pin "27") (pinfunction "GPA6_27") (pintype "bidirectional"))
    )
    (net (code "17") (name "/ENA_2") (class "Default")
      (node (ref "R78") (pin "1") (pinfunction "1_1") (pintype "passive"))
      (node (ref "R81") (pin "1") (pinfunction "1_1") (pintype "passive"))
      (node (ref "U$21") (pin "27") (pinfunction "GPA6_27") (pintype "bidirectional"))
    )
    (net (code "18") (name "/ENA_3") (class "Default")
      (node (ref "R89") (pin "1") (pinfunction "1_1") (pintype "passive"))
      (node (ref "R92") (pin "1") (pinfunction "1_1") (pintype "passive"))
      (node (ref "U$21") (pin "2") (pinfunction "GPB1_2") (pintype "bidirectional"))
    )
    (net (code "19") (name "/ENB_0") (class "Default")
      (node (ref "R40") (pin "1") (pinfunction "1_1") (pintype "passive"))
      (node (ref "R41") (pin "1") (pinfunction "1_1") (pintype "passive"))
      (node (ref "U$17") (pin "3") (pinfunction "GPB2_3") (pintype "bidirectional"))
    )
    (net (code "20") (name "/ENB_1") (class "Default")
      (node (ref "R68") (pin "1") (pinfunction "1_1") (pintype "passive"))
      (node (ref "R69") (pin "1") (pinfunction "1_1") (pintype "passive"))
      (node (ref "U$17") (pin "26") (pinfunction "GPA5_26") (pintype "bidirectional"))
    )
    (net (code "21") (name "/ENB_2") (class "Default")
      (node (ref "R79") (pin "1") (pinfunction "1_1") (pintype "passive"))
      (node (ref "R80") (pin "1") (pinfunction "1_1") (pintype "passive"))
      (node (ref "U$21") (pin "26") (pinfunction "GPA5_26") (pintype "bidirectional"))
    )
    (net (code "22") (name "/ENB_3") (class "Default")
      (node (ref "R90") (pin "1") (pinfunction "1_1") (pintype "passive"))
      (node (ref "R91") (pin "1") (pinfunction "1_1") (pintype "passive"))
      (node (ref "U$21") (pin "3") (pinfunction "GPB2_3") (pintype "bidirectional"))
    )
    (net (code "23") (name "/GND") (class "Default")
      (node (ref "3.3REG1") (pin "DRAIN") (pinfunction "GND_DRAIN") (pintype "bidirectional"))
      (node (ref "5REG") (pin "DRAIN") (pinfunction "GND_DRAIN") (pintype "bidirectional"))
      (node (ref "BB_CON") (pin "3") (pinfunction "P$3_3") (pintype "bidirectional"))
      (node (ref "BB_CON") (pin "5") (pinfunction "P$5_5") (pintype "bidirectional"))
      (node (ref "C1") (pin "1") (pinfunction "1_1") (pintype "passive"))
      (node (ref "C10") (pin "1") (pinfunction "1_1") (pintype "passive"))
      (node (ref "C11") (pin "2") (pinfunction "2_2") (pintype "passive"))
      (node (ref "C12") (pin "2") (pinfunction "2_2") (pintype "passive"))
      (node (ref "C13") (pin "1") (pinfunction "1_1") (pintype "passive"))
      (node (ref "C22") (pin "2") (pinfunction "2_2") (pintype "passive"))
      (node (ref "C28") (pin "2") (pinfunction "2_2") (pintype "passive"))
      (node (ref "C32") (pin "2") (pinfunction "2_2") (pintype "passive"))
      (node (ref "C35") (pin "2") (pinfunction "2_2") (pintype "passive"))
      (node (ref "C36") (pin "2") (pinfunction "2_2") (pintype "passive"))
      (node (ref "C37") (pin "2") (pinfunction "2_2") (pintype "passive"))
      (node (ref "C38") (pin "2") (pinfunction "2_2") (pintype "passive"))
      (node (ref "C39") (pin "2") (pinfunction "2_2") (pintype "passive"))
      (node (ref "C40") (pin "2") (pinfunction "2_2") (pintype "passive"))
      (node (ref "C41") (pin "2") (pinfunction "2_2") (pintype "passive"))
      (node (ref "C45") (pin "2") (pinfunction "2_2") (pintype "passive"))
      (node (ref "C8") (pin "2") (pinfunction "2_2") (pintype "passive"))
      (node (ref "C9") (pin "2") (pinfunction "2_2") (pintype "passive"))
      (node (ref "GND") (pin "P$1") (pinfunction "P$1_P$1") (pintype "bidirectional"))
      (node (ref "JP1") (pin "3") (pinfunction "3_3") (pintype "passive"))
      (node (ref "JP2") (pin "3") (pinfunction "3_3") (pintype "passive"))
      (node (ref "JP3") (pin "3") (pinfunction "3_3") (pintype "passive"))
      (node (ref "JP4") (pin "3") (pinfunction "3_3") (pintype "passive"))
      (node (ref "R45") (pin "2") (pinfunction "2_2") (pintype "passive"))
      (node (ref "R47") (pin "2") (pinfunction "2_2") (pintype "passive"))
      (node (ref "R49") (pin "2") (pinfunction "2_2") (pintype "passive"))
      (node (ref "R51") (pin "2") (pinfunction "2_2") (pintype "passive"))
      (node (ref "R53") (pin "2") (pinfunction "2_2") (pintype "passive"))
      (node (ref "R55") (pin "2") (pinfunction "2_2") (pintype "passive"))
      (node (ref "R57") (pin "2") (pinfunction "2_2") (pintype "passive"))
      (node (ref "R59") (pin "2") (pinfunction "2_2") (pintype "passive"))
      (node (ref "R60") (pin "1") (pinfunction "1_1") (pintype "passive"))
      (node (ref "R61") (pin "1") (pinfunction "1_1") (pintype "passive"))
      (node (ref "R71") (pin "1") (pinfunction "1_1") (pintype "passive"))
      (node (ref "R72") (pin "1") (pinfunction "1_1") (pintype "passive"))
      (node (ref "R82") (pin "1") (pinfunction "1_1") (pintype "passive"))
      (node (ref "R83") (pin "1") (pinfunction "1_1") (pintype "passive"))
      (node (ref "R93") (pin "1") (pinfunction "1_1") (pintype "passive"))
      (node (ref "R94") (pin "1") (pinfunction "1_1") (pintype "passive"))
      (node (ref "U$14") (pin "AGND") (pinfunction "AGND_AGND") (pintype "bidirectional"))
      (node (ref "U$14") (pin "GND") (pinfunction "GND_GND") (pintype "bidirectional"))
      (node (ref "U$14") (pin "GND2") (pinfunction "GND2_GND2") (pintype "bidirectional"))
      (node (ref "U$15") (pin "10") (pinfunction "GND_10") (pintype "power_in"))
      (node (ref "U$17") (pin "10") (pinfunction "VSS_10") (pintype "bidirectional"))
      (node (ref "U$17") (pin "15") (pinfunction "A0_15") (pintype "bidirectional"))
      (node (ref "U$17") (pin "16") (pinfunction "A1_16") (pintype "bidirectional"))
      (node (ref "U$17") (pin "17") (pinfunction "A2_17") (pintype "bidirectional"))
      (node (ref "U$19") (pin "2") (pinfunction "P$2_2") (pintype "bidirectional"))
      (node (ref "U$21") (pin "10") (pinfunction "VSS_10") (pintype "bidirectional"))
      (node (ref "U$21") (pin "15") (pinfunction "A0_15") (pintype "bidirectional"))
      (node (ref "U$21") (pin "16") (pinfunction "A1_16") (pintype "bidirectional"))
      (node (ref "U$8") (pin "1") (pinfunction "GND_1") (pintype "bidirectional"))
    )
    (net (code "24") (name "/INA_0") (class "Default")
      (node (ref "R63") (pin "2") (pinfunction "2_2") (pintype "passive"))
      (node (ref "U$17") (pin "1") (pinfunction "GPB0_1") (pintype "bidirectional"))
    )
    (net (code "25") (name "/INA_1") (class "Default")
      (node (ref "R74") (pin "2") (pinfunction "2_2") (pintype "passive"))
      (node (ref "U$17") (pin "28") (pinfunction "GPA7_28") (pintype "bidirectional"))
    )
    (net (code "26") (name "/INA_2") (class "Default")
      (node (ref "R85") (pin "2") (pinfunction "2_2") (pintype "passive"))
      (node (ref "U$21") (pin "28") (pinfunction "GPA7_28") (pintype "bidirectional"))
    )
    (net (code "27") (name "/INA_3") (class "Default")
      (node (ref "R96") (pin "2") (pinfunction "2_2") (pintype "passive"))
      (node (ref "U$21") (pin "1") (pinfunction "GPB0_1") (pintype "bidirectional"))
    )
    (net (code "28") (name "/INB_0") (class "Default")
      (node (ref "R62") (pin "2") (pinfunction "2_2") (pintype "passive"))
      (node (ref "U$17") (pin "4") (pinfunction "GPB3_4") (pintype "bidirectional"))
    )
    (net (code "29") (name "/INB_1") (class "Default")
      (node (ref "R73") (pin "2") (pinfunction "2_2") (pintype "passive"))
      (node (ref "U$17") (pin "25") (pinfunction "GPA4_25") (pintype "bidirectional"))
    )
    (net (code "30") (name "/INB_2") (class "Default")
      (node (ref "R84") (pin "2") (pinfunction "2_2") (pintype "passive"))
      (node (ref "U$21") (pin "25") (pinfunction "GPA4_25") (pintype "bidirectional"))
    )
    (net (code "31") (name "/INB_3") (class "Default")
      (node (ref "R95") (pin "2") (pinfunction "2_2") (pintype "passive"))
      (node (ref "U$21") (pin "4") (pinfunction "GPB3_4") (pintype "bidirectional"))
    )
    (net (code "32") (name "/INT1") (class "Default")
      (node (ref "U$14") (pin "9/CS") (pinfunction "9/CS_9/CS") (pintype "bidirectional"))
      (node (ref "U$17") (pin "20") (pinfunction "INTA_20") (pintype "bidirectional"))
    )
    (net (code "33") (name "/INT2") (class "Default")
      (node (ref "U$14") (pin "39/A20") (pinfunction "39/A20_39/A20") (pintype "bidirectional"))
      (node (ref "U$21") (pin "20") (pinfunction "INTA_20") (pintype "bidirectional"))
    )
    (net (code "34") (name "/M1QA-1") (class "Default")
      (node (ref "JP1") (pin "5") (pinfunction "5_5") (pintype "passive"))
      (node (ref "R58") (pin "2") (pinfunction "2_2") (pintype "passive"))
    )
    (net (code "35") (name "/M1QA-1OUT") (class "Default")
      (node (ref "R58") (pin "1") (pinfunction "1_1") (pintype "passive"))
      (node (ref "R59") (pin "1") (pinfunction "1_1") (pintype "passive"))
      (node (ref "U$14") (pin "17/A3") (pinfunction "17/A3_17/A3") (pintype "bidirectional"))
    )
    (net (code "36") (name "/M1QA-2") (class "Default")
      (node (ref "JP2") (pin "5") (pinfunction "5_5") (pintype "passive"))
      (node (ref "R52") (pin "2") (pinfunction "2_2") (pintype "passive"))
    )
    (net (code "37") (name "/M1QA-2OUT") (class "Default")
      (node (ref "R52") (pin "1") (pinfunction "1_1") (pintype "passive"))
      (node (ref "R53") (pin "1") (pinfunction "1_1") (pintype "passive"))
      (node (ref "U$14") (pin "27") (pinfunction "27_27") (pintype "bidirectional"))
    )
    (net (code "38") (name "/M1QA-3") (class "Default")
      (node (ref "JP3") (pin "5") (pinfunction "5_5") (pintype "passive"))
      (node (ref "R54") (pin "2") (pinfunction "2_2") (pintype "passive"))
    )
    (net (code "39") (name "/M1QA-3OUT") (class "Default")
      (node (ref "R54") (pin "1") (pinfunction "1_1") (pintype "passive"))
      (node (ref "R55") (pin "1") (pinfunction "1_1") (pintype "passive"))
      (node (ref "U$14") (pin "15/A1") (pinfunction "15/A1_15/A1") (pintype "bidirectional"))
    )
    (net (code "40") (name "/M1QA-4") (class "Default")
      (node (ref "JP4") (pin "5") (pinfunction "5_5") (pintype "passive"))
      (node (ref "R56") (pin "2") (pinfunction "2_2") (pintype "passive"))
    )
    (net (code "41") (name "/M1QA-4OUT") (class "Default")
      (node (ref "R56") (pin "1") (pinfunction "1_1") (pintype "passive"))
      (node (ref "R57") (pin "1") (pinfunction "1_1") (pintype "passive"))
      (node (ref "U$14") (pin "25") (pinfunction "25_25") (pintype "bidirectional"))
    )
    (net (code "42") (name "/M1QB-1") (class "Default")
      (node (ref "JP1") (pin "6") (pinfunction "6_6") (pintype "passive"))
      (node (ref "R50") (pin "2") (pinfunction "2_2") (pintype "passive"))
    )
    (net (code "43") (name "/M1QB-1OUT") (class "Default")
      (node (ref "R50") (pin "1") (pinfunction "1_1") (pintype "passive"))
      (node (ref "R51") (pin "1") (pinfunction "1_1") (pintype "passive"))
      (node (ref "U$14") (pin "16/A2") (pinfunction "16/A2_16/A2") (pintype "bidirectional"))
    )
    (net (code "44") (name "/M1QB-2") (class "Default")
      (node (ref "JP2") (pin "6") (pinfunction "6_6") (pintype "passive"))
      (node (ref "R44") (pin "2") (pinfunction "2_2") (pintype "passive"))
    )
    (net (code "45") (name "/M1QB-2OUT") (class "Default")
      (node (ref "R44") (pin "1") (pinfunction "1_1") (pintype "passive"))
      (node (ref "R45") (pin "1") (pinfunction "1_1") (pintype "passive"))
      (node (ref "U$14") (pin "28") (pinfunction "28_28") (pintype "bidirectional"))
    )
    (net (code "46") (name "/M1QB-3") (class "Default")
      (node (ref "JP3") (pin "6") (pinfunction "6_6") (pintype "passive"))
      (node (ref "R46") (pin "2") (pinfunction "2_2") (pintype "passive"))
    )
    (net (code "47") (name "/M1QB-3OUT") (class "Default")
      (node (ref "R46") (pin "1") (pinfunction "1_1") (pintype "passive"))
      (node (ref "R47") (pin "1") (pinfunction "1_1") (pintype "passive"))
      (node (ref "U$14") (pin "14/A0") (pinfunction "14/A0_14/A0") (pintype "bidirectional"))
    )
    (net (code "48") (name "/M1QB-4") (class "Default")
      (node (ref "JP4") (pin "6") (pinfunction "6_6") (pintype "passive"))
      (node (ref "R48") (pin "2") (pinfunction "2_2") (pintype "passive"))
    )
    (net (code "49") (name "/M1QB-4OUT") (class "Default")
      (node (ref "R48") (pin "1") (pinfunction "1_1") (pintype "passive"))
      (node (ref "R49") (pin "1") (pinfunction "1_1") (pintype "passive"))
      (node (ref "U$14") (pin "26") (pinfunction "26_26") (pintype "bidirectional"))
    )
    (net (code "50") (name "/N$38") (class "Default")
      (node (ref "C13") (pin "2") (pinfunction "2_2") (pintype "passive"))
      (node (ref "R32") (pin "1") (pinfunction "1_1") (pintype "passive"))
      (node (ref "U$8") (pin "7") (pinfunction "VREF2_7") (pintype "bidirectional"))
      (node (ref "U$8") (pin "8") (pinfunction "EN_8") (pintype "bidirectional"))
    )
    (net (code "51") (name "/OUTA_0") (class "Default")
      (node (ref "GREEN_DIR") (pin "C") (pinfunction "C_C") (pintype "passive"))
      (node (ref "JP1") (pin "1") (pinfunction "1_1") (pintype "passive"))
      (node (ref "RED_DIR") (pin "A") (pinfunction "A_A") (pintype "passive"))
      (node (ref "U$16") (pin "1") (pinfunction "OUTA_1") (pintype "bidirectional"))
      (node (ref "U$16") (pin "24") (pinfunction "OUTA_24") (pintype "bidirectional"))
      (node (ref "U$16") (pin "25") (pinfunction "OUTA_25") (pintype "bidirectional"))
      (node (ref "U$16") (pin "30") (pinfunction "OUTA_30") (pintype "bidirectional"))
      (node (ref "U$16") (pin "OUTA") (pinfunction "OUTA_OUTA") (pintype "bidirectional"))
      (node (ref "U$16") (pin "OUTA@1") (pinfunction "OUTA_OUTA@1") (pintype "bidirectional"))
    )
    (net (code "52") (name "/OUTA_1") (class "Default")
      (node (ref "GREEN_DIR1") (pin "C") (pinfunction "C_C") (pintype "passive"))
      (node (ref "JP2") (pin "1") (pinfunction "1_1") (pintype "passive"))
      (node (ref "RED_DIR1") (pin "A") (pinfunction "A_A") (pintype "passive"))
      (node (ref "U$23") (pin "1") (pinfunction "OUTA_1") (pintype "bidirectional"))
      (node (ref "U$23") (pin "24") (pinfunction "OUTA_24") (pintype "bidirectional"))
      (node (ref "U$23") (pin "25") (pinfunction "OUTA_25") (pintype "bidirectional"))
      (node (ref "U$23") (pin "30") (pinfunction "OUTA_30") (pintype "bidirectional"))
      (node (ref "U$23") (pin "OUTA") (pinfunction "OUTA_OUTA") (pintype "bidirectional"))
      (node (ref "U$23") (pin "OUTA@1") (pinfunction "OUTA_OUTA@1") (pintype "bidirectional"))
    )
    (net (code "53") (name "/OUTA_2") (class "Default")
      (node (ref "GREEN_DIR2") (pin "C") (pinfunction "C_C") (pintype "passive"))
      (node (ref "JP3") (pin "1") (pinfunction "1_1") (pintype "passive"))
      (node (ref "RED_DIR2") (pin "A") (pinfunction "A_A") (pintype "passive"))
      (node (ref "U$25") (pin "1") (pinfunction "OUTA_1") (pintype "bidirectional"))
      (node (ref "U$25") (pin "24") (pinfunction "OUTA_24") (pintype "bidirectional"))
      (node (ref "U$25") (pin "25") (pinfunction "OUTA_25") (pintype "bidirectional"))
      (node (ref "U$25") (pin "30") (pinfunction "OUTA_30") (pintype "bidirectional"))
      (node (ref "U$25") (pin "OUTA") (pinfunction "OUTA_OUTA") (pintype "bidirectional"))
      (node (ref "U$25") (pin "OUTA@1") (pinfunction "OUTA_OUTA@1") (pintype "bidirectional"))
    )
    (net (code "54") (name "/OUTA_3") (class "Default")
      (node (ref "GREEN_DIR3") (pin "C") (pinfunction "C_C") (pintype "passive"))
      (node (ref "JP4") (pin "1") (pinfunction "1_1") (pintype "passive"))
      (node (ref "RED_DIR3") (pin "A") (pinfunction "A_A") (pintype "passive"))
      (node (ref "U$27") (pin "1") (pinfunction "OUTA_1") (pintype "bidirectional"))
      (node (ref "U$27") (pin "24") (pinfunction "OUTA_24") (pintype "bidirectional"))
      (node (ref "U$27") (pin "25") (pinfunction "OUTA_25") (pintype "bidirectional"))
      (node (ref "U$27") (pin "30") (pinfunction "OUTA_30") (pintype "bidirectional"))
      (node (ref "U$27") (pin "OUTA") (pinfunction "OUTA_OUTA") (pintype "bidirectional"))
      (node (ref "U$27") (pin "OUTA@1") (pinfunction "OUTA_OUTA@1") (pintype "bidirectional"))
    )
    (net (code "55") (name "/OUTB_0") (class "Default")
      (node (ref "JP1") (pin "2") (pinfunction "2_2") (pintype "passive"))
      (node (ref "R38") (pin "1") (pinfunction "1_1") (pintype "passive"))
      (node (ref "U$16") (pin "15") (pinfunction "OUTB_15") (pintype "bidirectional"))
      (node (ref "U$16") (pin "16") (pinfunction "OUTB_16") (pintype "bidirectional"))
      (node (ref "U$16") (pin "21") (pinfunction "OUTB_21") (pintype "bidirectional"))
      (node (ref "U$16") (pin "22") (pinfunction "OUTB_22") (pintype "bidirectional"))
      (node (ref "U$16") (pin "OUTB") (pinfunction "OUTB_OUTB") (pintype "bidirectional"))
      (node (ref "U$16") (pin "OUTB@1") (pinfunction "OUTB_OUTB@1") (pintype "bidirectional"))
    )
    (net (code "56") (name "/OUTB_1") (class "Default")
      (node (ref "JP2") (pin "2") (pinfunction "2_2") (pintype "passive"))
      (node (ref "R66") (pin "1") (pinfunction "1_1") (pintype "passive"))
      (node (ref "U$23") (pin "15") (pinfunction "OUTB_15") (pintype "bidirectional"))
      (node (ref "U$23") (pin "16") (pinfunction "OUTB_16") (pintype "bidirectional"))
      (node (ref "U$23") (pin "21") (pinfunction "OUTB_21") (pintype "bidirectional"))
      (node (ref "U$23") (pin "22") (pinfunction "OUTB_22") (pintype "bidirectional"))
      (node (ref "U$23") (pin "OUTB") (pinfunction "OUTB_OUTB") (pintype "bidirectional"))
      (node (ref "U$23") (pin "OUTB@1") (pinfunction "OUTB_OUTB@1") (pintype "bidirectional"))
    )
    (net (code "57") (name "/OUTB_2") (class "Default")
      (node (ref "JP3") (pin "2") (pinfunction "2_2") (pintype "passive"))
      (node (ref "R77") (pin "1") (pinfunction "1_1") (pintype "passive"))
      (node (ref "U$25") (pin "15") (pinfunction "OUTB_15") (pintype "bidirectional"))
      (node (ref "U$25") (pin "16") (pinfunction "OUTB_16") (pintype "bidirectional"))
      (node (ref "U$25") (pin "21") (pinfunction "OUTB_21") (pintype "bidirectional"))
      (node (ref "U$25") (pin "22") (pinfunction "OUTB_22") (pintype "bidirectional"))
      (node (ref "U$25") (pin "OUTB") (pinfunction "OUTB_OUTB") (pintype "bidirectional"))
      (node (ref "U$25") (pin "OUTB@1") (pinfunction "OUTB_OUTB@1") (pintype "bidirectional"))
    )
    (net (code "58") (name "/OUTB_3") (class "Default")
      (node (ref "JP4") (pin "2") (pinfunction "2_2") (pintype "passive"))
      (node (ref "R88") (pin "1") (pinfunction "1_1") (pintype "passive"))
      (node (ref "U$27") (pin "15") (pinfunction "OUTB_15") (pintype "bidirectional"))
      (node (ref "U$27") (pin "16") (pinfunction "OUTB_16") (pintype "bidirectional"))
      (node (ref "U$27") (pin "21") (pinfunction "OUTB_21") (pintype "bidirectional"))
      (node (ref "U$27") (pin "22") (pinfunction "OUTB_22") (pintype "bidirectional"))
      (node (ref "U$27") (pin "OUTB") (pinfunction "OUTB_OUTB") (pintype "bidirectional"))
      (node (ref "U$27") (pin "OUTB@1") (pinfunction "OUTB_OUTB@1") (pintype "bidirectional"))
    )
    (net (code "59") (name "/PWM0") (class "Default")
      (node (ref "R35") (pin "1") (pinfunction "1_1") (pintype "passive"))
      (node (ref "R60") (pin "2") (pinfunction "2_2") (pintype "passive"))
      (node (ref "U$14") (pin "2") (pinfunction "2_2") (pintype "bidirectional"))
    )
    (net (code "60") (name "/PWM1") (class "Default")
      (node (ref "R64") (pin "1") (pinfunction "1_1") (pintype "passive"))
      (node (ref "R71") (pin "2") (pinfunction "2_2") (pintype "passive"))
      (node (ref "U$14") (pin "3/CANTX") (pinfunction "3/CANTX_3/CANTX") (pintype "bidirectional"))
    )
    (net (code "61") (name "/PWM2") (class "Default")
      (node (ref "R75") (pin "1") (pinfunction "1_1") (pintype "passive"))
      (node (ref "R82") (pin "2") (pinfunction "2_2") (pintype "passive"))
      (node (ref "U$14") (pin "10/CS") (pinfunction "10/CS_10/CS") (pintype "bidirectional"))
    )
    (net (code "62") (name "/PWM3") (class "Default")
      (node (ref "R86") (pin "1") (pinfunction "1_1") (pintype "passive"))
      (node (ref "R93") (pin "2") (pinfunction "2_2") (pintype "passive"))
      (node (ref "U$14") (pin "29") (pinfunction "29_29") (pintype "bidirectional"))
    )
    (net (code "63") (name "/RTS") (class "Default")
      (node (ref "R28") (pin "1") (pinfunction "1_1") (pintype "passive"))
      (node (ref "U$14") (pin "35/A16") (pinfunction "35/A16_35/A16") (pintype "bidirectional"))
    )
    (net (code "64") (name "/RX") (class "Default")
      (node (ref "U$14") (pin "34/A15") (pinfunction "34/A15_34/A15") (pintype "bidirectional"))
      (node (ref "U$15") (pin "2") (pinfunction "DOUT_2") (pintype "output"))
    )
    (net (code "65") (name "/SCL") (class "Default")
      (node (ref "R27") (pin "1") (pinfunction "1_1") (pintype "passive"))
      (node (ref "U$14") (pin "19/A5/SCL") (pinfunction "19/A5/SCL_19/A5/SCL") (pintype "bidirectional"))
      (node (ref "U$8") (pin "3") (pinfunction "SCL1_3") (pintype "bidirectional"))
    )
    (net (code "66") (name "/SCL-H") (class "Default")
      (node (ref "R33") (pin "1") (pinfunction "1_1") (pintype "passive"))
      (node (ref "U$17") (pin "12") (pinfunction "SCK_12") (pintype "bidirectional"))
      (node (ref "U$21") (pin "12") (pinfunction "SCK_12") (pintype "bidirectional"))
      (node (ref "U$8") (pin "6") (pinfunction "SCL2_6") (pintype "bidirectional"))
    )
    (net (code "67") (name "/SDA") (class "Default")
      (node (ref "R7") (pin "1") (pinfunction "1_1") (pintype "passive"))
      (node (ref "U$14") (pin "18/A4/SDA") (pinfunction "18/A4/SDA_18/A4/SDA") (pintype "bidirectional"))
      (node (ref "U$8") (pin "4") (pinfunction "SDA1_4") (pintype "bidirectional"))
    )
    (net (code "68") (name "/SDA-H") (class "Default")
      (node (ref "R34") (pin "1") (pinfunction "1_1") (pintype "passive"))
      (node (ref "U$17") (pin "13") (pinfunction "SDA_13") (pintype "bidirectional"))
      (node (ref "U$21") (pin "13") (pinfunction "SDA_13") (pintype "bidirectional"))
      (node (ref "U$8") (pin "5") (pinfunction "SDA2_5") (pintype "bidirectional"))
    )
    (net (code "69") (name "/TX") (class "Default")
      (node (ref "U$14") (pin "33/A14") (pinfunction "33/A14_33/A14") (pintype "bidirectional"))
      (node (ref "U$15") (pin "3") (pinfunction "DIN_3") (pintype "input"))
    )
    (net (code "70") (name "/XBRST") (class "Default")
      (node (ref "U$15") (pin "5") (pinfunction "RESET_5") (pintype "input"))
    )
    (net (code "71") (name "Net-(BB_CON-P$1)") (class "Default")
      (node (ref "BB_CON") (pin "1") (pinfunction "P$1_1") (pintype "bidirectional"))
      (node (ref "R20") (pin "2") (pinfunction "2_2") (pintype "passive"))
    )
    (net (code "72") (name "Net-(BB_CON-P$4)") (class "Default")
      (node (ref "BB_CON") (pin "4") (pinfunction "P$4_4") (pintype "bidirectional"))
      (node (ref "R19") (pin "2") (pinfunction "2_2") (pintype "passive"))
    )
    (net (code "73") (name "Net-(DRIB-P$2)") (class "Default")
      (node (ref "DRIB") (pin "2") (pinfunction "P$2_2") (pintype "bidirectional"))
      (node (ref "DRIB_TRAN") (pin "DRAIN") (pinfunction "D_DRAIN") (pintype "bidirectional"))
    )
    (net (code "74") (name "Net-(GREEN_DIR-PadA)") (class "Default")
      (node (ref "GREEN_DIR") (pin "A") (pinfunction "A_A") (pintype "passive"))
      (node (ref "R38") (pin "2") (pinfunction "2_2") (pintype "passive"))
      (node (ref "RED_DIR") (pin "C") (pinfunction "C_C") (pintype "passive"))
    )
    (net (code "75") (name "Net-(GREEN_DIR1-PadA)") (class "Default")
      (node (ref "GREEN_DIR1") (pin "A") (pinfunction "A_A") (pintype "passive"))
      (node (ref "R66") (pin "2") (pinfunction "2_2") (pintype "passive"))
      (node (ref "RED_DIR1") (pin "C") (pinfunction "C_C") (pintype "passive"))
    )
    (net (code "76") (name "Net-(GREEN_DIR2-PadA)") (class "Default")
      (node (ref "GREEN_DIR2") (pin "A") (pinfunction "A_A") (pintype "passive"))
      (node (ref "R77") (pin "2") (pinfunction "2_2") (pintype "passive"))
      (node (ref "RED_DIR2") (pin "C") (pinfunction "C_C") (pintype "passive"))
    )
    (net (code "77") (name "Net-(GREEN_DIR3-PadA)") (class "Default")
      (node (ref "GREEN_DIR3") (pin "A") (pinfunction "A_A") (pintype "passive"))
      (node (ref "R88") (pin "2") (pinfunction "2_2") (pintype "passive"))
      (node (ref "RED_DIR3") (pin "C") (pinfunction "C_C") (pintype "passive"))
    )
    (net (code "78") (name "Net-(PW_LED1-PadC)") (class "Default")
      (node (ref "PW_LED1") (pin "C") (pinfunction "C_C") (pintype "passive"))
      (node (ref "R21") (pin "2") (pinfunction "2_2") (pintype "passive"))
    )
    (net (code "79") (name "Net-(U$15-CTS)") (class "Default")
      (node (ref "R30") (pin "2") (pinfunction "2_2") (pintype "passive"))
      (node (ref "U$15") (pin "12") (pinfunction "CTS_12") (pintype "output"))
    )
    (net (code "80") (name "Net-(U$15-RTS)") (class "Default")
      (node (ref "R28") (pin "2") (pinfunction "2_2") (pintype "passive"))
      (node (ref "U$15") (pin "16") (pinfunction "RTS_16") (pintype "input"))
    )
    (net (code "81") (name "Net-(U$16-CP)") (class "Default")
      (node (ref "U$16") (pin "11") (pinfunction "CP_11") (pintype "bidirectional"))
      (node (ref "U$20") (pin "1") (pinfunction "G_1") (pintype "bidirectional"))
    )
    (net (code "82") (name "Net-(U$16-CS)") (class "Default")
      (node (ref "R36") (pin "2") (pinfunction "2_2") (pintype "passive"))
      (node (ref "R61") (pin "2") (pinfunction "2_2") (pintype "passive"))
      (node (ref "U$16") (pin "8") (pinfunction "CS_8") (pintype "bidirectional"))
    )
    (net (code "83") (name "Net-(U$16-ENA{slash}DIAGA)") (class "Default")
      (node (ref "R39") (pin "2") (pinfunction "2_2") (pintype "passive"))
      (node (ref "U$16") (pin "5") (pinfunction "ENA/DIAGA_5") (pintype "bidirectional"))
    )
    (net (code "84") (name "Net-(U$16-ENB{slash}DIAGB)") (class "Default")
      (node (ref "R40") (pin "2") (pinfunction "2_2") (pintype "passive"))
      (node (ref "U$16") (pin "9") (pinfunction "ENB/DIAGB_9") (pintype "bidirectional"))
    )
    (net (code "85") (name "Net-(U$16-INA)") (class "Default")
      (node (ref "R63") (pin "1") (pinfunction "1_1") (pintype "passive"))
      (node (ref "U$16") (pin "4") (pinfunction "INA_4") (pintype "bidirectional"))
    )
    (net (code "86") (name "Net-(U$16-INB)") (class "Default")
      (node (ref "R62") (pin "1") (pinfunction "1_1") (pintype "passive"))
      (node (ref "U$16") (pin "10") (pinfunction "INB_10") (pintype "bidirectional"))
    )
    (net (code "87") (name "Net-(U$16-PWM)") (class "Default")
      (node (ref "R35") (pin "2") (pinfunction "2_2") (pintype "passive"))
      (node (ref "U$16") (pin "7") (pinfunction "PWM_7") (pintype "bidirectional"))
    )
    (net (code "88") (name "Net-(U$20-S)") (class "Default")
      (node (ref "C17") (pin "1") (pinfunction "1_1") (pintype "passive"))
      (node (ref "C24") (pin "1") (pinfunction "1_1") (pintype "passive"))
      (node (ref "U$16") (pin "13") (pinfunction "VCC_13") (pintype "bidirectional"))
      (node (ref "U$16") (pin "14") (pinfunction "VCC_14") (pintype "bidirectional"))
      (node (ref "U$16") (pin "2") (pinfunction "VCC_2") (pintype "bidirectional"))
      (node (ref "U$16") (pin "23") (pinfunction "VCC_23") (pintype "bidirectional"))
      (node (ref "U$16") (pin "3") (pinfunction "VCC_3") (pintype "bidirectional"))
      (node (ref "U$16") (pin "VCC") (pinfunction "VCC_VCC") (pintype "bidirectional"))
      (node (ref "U$16") (pin "VCC@1") (pinfunction "VCC_VCC@1") (pintype "bidirectional"))
      (node (ref "U$20") (pin "3") (pinfunction "S_3") (pintype "bidirectional"))
    )
    (net (code "89") (name "Net-(U$23-CP)") (class "Default")
      (node (ref "U$23") (pin "11") (pinfunction "CP_11") (pintype "bidirectional"))
      (node (ref "U$24") (pin "1") (pinfunction "G_1") (pintype "bidirectional"))
    )
    (net (code "90") (name "Net-(U$23-CS)") (class "Default")
      (node (ref "R65") (pin "2") (pinfunction "2_2") (pintype "passive"))
      (node (ref "R72") (pin "2") (pinfunction "2_2") (pintype "passive"))
      (node (ref "U$23") (pin "8") (pinfunction "CS_8") (pintype "bidirectional"))
    )
    (net (code "91") (name "Net-(U$23-ENA{slash}DIAGA)") (class "Default")
      (node (ref "R67") (pin "2") (pinfunction "2_2") (pintype "passive"))
      (node (ref "U$23") (pin "5") (pinfunction "ENA/DIAGA_5") (pintype "bidirectional"))
    )
    (net (code "92") (name "Net-(U$23-ENB{slash}DIAGB)") (class "Default")
      (node (ref "R68") (pin "2") (pinfunction "2_2") (pintype "passive"))
      (node (ref "U$23") (pin "9") (pinfunction "ENB/DIAGB_9") (pintype "bidirectional"))
    )
    (net (code "93") (name "Net-(U$23-INA)") (class "Default")
      (node (ref "R74") (pin "1") (pinfunction "1_1") (pintype "passive"))
      (node (ref "U$23") (pin "4") (pinfunction "INA_4") (pintype "bidirectional"))
    )
    (net (code "94") (name "Net-(U$23-INB)") (class "Default")
      (node (ref "R73") (pin "1") (pinfunction "1_1") (pintype "passive"))
      (node (ref "U$23") (pin "10") (pinfunction "INB_10") (pintype "bidirectional"))
    )
    (net (code "95") (name "Net-(U$23-PWM)") (class "Default")
      (node (ref "R64") (pin "2") (pinfunction "2_2") (pintype "passive"))
      (node (ref "U$23") (pin "7") (pinfunction "PWM_7") (pintype "bidirectional"))
    )
    (net (code "96") (name "Net-(U$24-S)") (class "Default")
      (node (ref "C26") (pin "1") (pinfunction "1_1") (pintype "passive"))
      (node (ref "C27") (pin "1") (pinfunction "1_1") (pintype "passive"))
      (node (ref "U$23") (pin "13") (pinfunction "VCC_13") (pintype "bidirectional"))
      (node (ref "U$23") (pin "14") (pinfunction "VCC_14") (pintype "bidirectional"))
      (node (ref "U$23") (pin "2") (pinfunction "VCC_2") (pintype "bidirectional"))
      (node (ref "U$23") (pin "23") (pinfunction "VCC_23") (pintype "bidirectional"))
      (node (ref "U$23") (pin "3") (pinfunction "VCC_3") (pintype "bidirectional"))
      (node (ref "U$23") (pin "VCC") (pinfunction "VCC_VCC") (pintype "bidirectional"))
      (node (ref "U$23") (pin "VCC@1") (pinfunction "VCC_VCC@1") (pintype "bidirectional"))
      (node (ref "U$24") (pin "3") (pinfunction "S_3") (pintype "bidirectional"))
    )
    (net (code "97") (name "Net-(U$25-CP)") (class "Default")
      (node (ref "U$25") (pin "11") (pinfunction "CP_11") (pintype "bidirectional"))
      (node (ref "U$26") (pin "1") (pinfunction "G_1") (pintype "bidirectional"))
    )
    (net (code "98") (name "Net-(U$25-CS)") (class "Default")
      (node (ref "R76") (pin "2") (pinfunction "2_2") (pintype "passive"))
      (node (ref "R83") (pin "2") (pinfunction "2_2") (pintype "passive"))
      (node (ref "U$25") (pin "8") (pinfunction "CS_8") (pintype "bidirectional"))
    )
    (net (code "99") (name "Net-(U$25-ENA{slash}DIAGA)") (class "Default")
      (node (ref "R78") (pin "2") (pinfunction "2_2") (pintype "passive"))
      (node (ref "U$25") (pin "5") (pinfunction "ENA/DIAGA_5") (pintype "bidirectional"))
    )
    (net (code "100") (name "Net-(U$25-ENB{slash}DIAGB)") (class "Default")
      (node (ref "R79") (pin "2") (pinfunction "2_2") (pintype "passive"))
      (node (ref "U$25") (pin "9") (pinfunction "ENB/DIAGB_9") (pintype "bidirectional"))
    )
    (net (code "101") (name "Net-(U$25-INA)") (class "Default")
      (node (ref "R85") (pin "1") (pinfunction "1_1") (pintype "passive"))
      (node (ref "U$25") (pin "4") (pinfunction "INA_4") (pintype "bidirectional"))
    )
    (net (code "102") (name "Net-(U$25-INB)") (class "Default")
      (node (ref "R84") (pin "1") (pinfunction "1_1") (pintype "passive"))
      (node (ref "U$25") (pin "10") (pinfunction "INB_10") (pintype "bidirectional"))
    )
    (net (code "103") (name "Net-(U$25-PWM)") (class "Default")
      (node (ref "R75") (pin "2") (pinfunction "2_2") (pintype "passive"))
      (node (ref "U$25") (pin "7") (pinfunction "PWM_7") (pintype "bidirectional"))
    )
    (net (code "104") (name "Net-(U$26-S)") (class "Default")
      (node (ref "C30") (pin "1") (pinfunction "1_1") (pintype "passive"))
      (node (ref "C31") (pin "1") (pinfunction "1_1") (pintype "passive"))
      (node (ref "U$25") (pin "13") (pinfunction "VCC_13") (pintype "bidirectional"))
      (node (ref "U$25") (pin "14") (pinfunction "VCC_14") (pintype "bidirectional"))
      (node (ref "U$25") (pin "2") (pinfunction "VCC_2") (pintype "bidirectional"))
      (node (ref "U$25") (pin "23") (pinfunction "VCC_23") (pintype "bidirectional"))
      (node (ref "U$25") (pin "3") (pinfunction "VCC_3") (pintype "bidirectional"))
      (node (ref "U$25") (pin "VCC") (pinfunction "VCC_VCC") (pintype "bidirectional"))
      (node (ref "U$25") (pin "VCC@1") (pinfunction "VCC_VCC@1") (pintype "bidirectional"))
      (node (ref "U$26") (pin "3") (pinfunction "S_3") (pintype "bidirectional"))
    )
    (net (code "105") (name "Net-(U$27-CP)") (class "Default")
      (node (ref "U$27") (pin "11") (pinfunction "CP_11") (pintype "bidirectional"))
      (node (ref "U$28") (pin "1") (pinfunction "G_1") (pintype "bidirectional"))
    )
    (net (code "106") (name "Net-(U$27-CS)") (class "Default")
      (node (ref "R87") (pin "2") (pinfunction "2_2") (pintype "passive"))
      (node (ref "R94") (pin "2") (pinfunction "2_2") (pintype "passive"))
      (node (ref "U$27") (pin "8") (pinfunction "CS_8") (pintype "bidirectional"))
    )
    (net (code "107") (name "Net-(U$27-ENA{slash}DIAGA)") (class "Default")
      (node (ref "R89") (pin "2") (pinfunction "2_2") (pintype "passive"))
      (node (ref "U$27") (pin "5") (pinfunction "ENA/DIAGA_5") (pintype "bidirectional"))
    )
    (net (code "108") (name "Net-(U$27-ENB{slash}DIAGB)") (class "Default")
      (node (ref "R90") (pin "2") (pinfunction "2_2") (pintype "passive"))
      (node (ref "U$27") (pin "9") (pinfunction "ENB/DIAGB_9") (pintype "bidirectional"))
    )
    (net (code "109") (name "Net-(U$27-INA)") (class "Default")
      (node (ref "R96") (pin "1") (pinfunction "1_1") (pintype "passive"))
      (node (ref "U$27") (pin "4") (pinfunction "INA_4") (pintype "bidirectional"))
    )
    (net (code "110") (name "Net-(U$27-INB)") (class "Default")
      (node (ref "R95") (pin "1") (pinfunction "1_1") (pintype "passive"))
      (node (ref "U$27") (pin "10") (pinfunction "INB_10") (pintype "bidirectional"))
    )
    (net (code "111") (name "Net-(U$27-PWM)") (class "Default")
      (node (ref "R86") (pin "2") (pinfunction "2_2") (pintype "passive"))
      (node (ref "U$27") (pin "7") (pinfunction "PWM_7") (pintype "bidirectional"))
    )
    (net (code "112") (name "Net-(U$28-S)") (class "Default")
      (node (ref "C43") (pin "1") (pinfunction "1_1") (pintype "passive"))
      (node (ref "C44") (pin "1") (pinfunction "1_1") (pintype "passive"))
      (node (ref "U$27") (pin "13") (pinfunction "VCC_13") (pintype "bidirectional"))
      (node (ref "U$27") (pin "14") (pinfunction "VCC_14") (pintype "bidirectional"))
      (node (ref "U$27") (pin "2") (pinfunction "VCC_2") (pintype "bidirectional"))
      (node (ref "U$27") (pin "23") (pinfunction "VCC_23") (pintype "bidirectional"))
      (node (ref "U$27") (pin "3") (pinfunction "VCC_3") (pintype "bidirectional"))
      (node (ref "U$27") (pin "VCC") (pinfunction "VCC_VCC") (pintype "bidirectional"))
      (node (ref "U$27") (pin "VCC@1") (pinfunction "VCC_VCC@1") (pintype "bidirectional"))
      (node (ref "U$28") (pin "3") (pinfunction "S_3") (pintype "bidirectional"))
    )
    (net (code "113") (name "unconnected-(U$14-A21{slash}DAC0-Pad21{slash}DAC0)") (class "Default")
      (node (ref "U$14") (pin "21/DAC0") (pinfunction "A21/DAC0_21/DAC0") (pintype "bidirectional"))
    )
    (net (code "114") (name "unconnected-(U$14-Pad0{slash}RX)") (class "Default")
      (node (ref "U$14") (pin "0/RX") (pinfunction "0/RX_0/RX") (pintype "bidirectional"))
    )
    (net (code "115") (name "unconnected-(U$14-Pad1{slash}TX)") (class "Default")
      (node (ref "U$14") (pin "1/TX") (pinfunction "1/TX_1/TX") (pintype "bidirectional"))
    )
    (net (code "116") (name "unconnected-(U$14-Pad3V3)") (class "Default")
      (node (ref "U$14") (pin "3V3") (pinfunction "3V3_3V3") (pintype "bidirectional"))
    )
    (net (code "117") (name "unconnected-(U$14-Pad3V3_2)") (class "Default")
      (node (ref "U$14") (pin "3V3_2") (pinfunction "3V3_2_3V3_2") (pintype "bidirectional"))
    )
    (net (code "118") (name "unconnected-(U$14-Pad3V3_LO)") (class "Default")
      (node (ref "U$14") (pin "3V3_LO") (pinfunction "3V3_LO_3V3_LO") (pintype "bidirectional"))
    )
    (net (code "119") (name "unconnected-(U$14-Pad4{slash}CANRX)") (class "Default")
      (node (ref "U$14") (pin "4/CANRX") (pinfunction "4/CANRX_4/CANRX") (pintype "bidirectional"))
    )
    (net (code "120") (name "unconnected-(U$14-Pad5)") (class "Default")
      (node (ref "U$14") (pin "5") (pinfunction "5_5") (pintype "bidirectional"))
    )
    (net (code "121") (name "unconnected-(U$14-Pad7)") (class "Default")
      (node (ref "U$14") (pin "7") (pinfunction "7_7") (pintype "bidirectional"))
    )
    (net (code "122") (name "unconnected-(U$14-Pad8)") (class "Default")
      (node (ref "U$14") (pin "8") (pinfunction "8_8") (pintype "bidirectional"))
    )
    (net (code "123") (name "unconnected-(U$14-Pad11{slash}MOSI)") (class "Default")
      (node (ref "U$14") (pin "11/MOSI") (pinfunction "11/MOSI_11/MOSI") (pintype "bidirectional"))
    )
    (net (code "124") (name "unconnected-(U$14-Pad12{slash}MISO)") (class "Default")
      (node (ref "U$14") (pin "12/MISO") (pinfunction "12/MISO_12/MISO") (pintype "bidirectional"))
    )
    (net (code "125") (name "unconnected-(U$14-Pad13{slash}SCK)") (class "Default")
      (node (ref "U$14") (pin "13/SCK") (pinfunction "13/SCK_13/SCK") (pintype "bidirectional"))
    )
    (net (code "126") (name "unconnected-(U$14-Pad20{slash}A6)") (class "Default")
      (node (ref "U$14") (pin "20/A6") (pinfunction "20/A6_20/A6") (pintype "bidirectional"))
    )
    (net (code "127") (name "unconnected-(U$14-Pad30)") (class "Default")
      (node (ref "U$14") (pin "30") (pinfunction "30_30") (pintype "bidirectional"))
    )
    (net (code "128") (name "unconnected-(U$14-Pad38{slash}A19)") (class "Default")
      (node (ref "U$14") (pin "38/A19") (pinfunction "38/A19_38/A19") (pintype "bidirectional"))
    )
    (net (code "129") (name "unconnected-(U$14-PadA10)") (class "Default")
      (node (ref "U$14") (pin "A10") (pinfunction "A10_A10") (pintype "bidirectional"))
    )
    (net (code "130") (name "unconnected-(U$14-PadA11)") (class "Default")
      (node (ref "U$14") (pin "A11") (pinfunction "A11_A11") (pintype "bidirectional"))
    )
    (net (code "131") (name "unconnected-(U$14-PadA22{slash}DAC1)") (class "Default")
      (node (ref "U$14") (pin "A22/DAC1") (pinfunction "A22/DAC1_A22/DAC1") (pintype "bidirectional"))
    )
    (net (code "132") (name "unconnected-(U$14-PadAREF)") (class "Default")
      (node (ref "U$14") (pin "AREF") (pinfunction "AREF_AREF") (pintype "bidirectional"))
    )
    (net (code "133") (name "unconnected-(U$14-PadGND3)") (class "Default")
      (node (ref "U$14") (pin "GND3") (pinfunction "GND3_GND3") (pintype "bidirectional"))
    )
    (net (code "134") (name "unconnected-(U$14-PadPROG)") (class "Default")
      (node (ref "U$14") (pin "PROG") (pinfunction "PROG_PROG") (pintype "bidirectional"))
    )
    (net (code "135") (name "unconnected-(U$14-PadRESET)") (class "Default")
      (node (ref "U$14") (pin "RESET") (pinfunction "RESET_RESET") (pintype "bidirectional"))
    )
    (net (code "136") (name "unconnected-(U$14-PadU5V)") (class "Default")
      (node (ref "U$14") (pin "U5V") (pinfunction "U5V_U5V") (pintype "bidirectional"))
    )
    (net (code "137") (name "unconnected-(U$14-PadUD+)") (class "Default")
      (node (ref "U$14") (pin "UD+") (pinfunction "UD+_UD+") (pintype "bidirectional"))
    )
    (net (code "138") (name "unconnected-(U$14-PadUD-)") (class "Default")
      (node (ref "U$14") (pin "UD-") (pinfunction "UD-_UD-") (pintype "bidirectional"))
    )
    (net (code "139") (name "unconnected-(U$14-PadUGND1)") (class "Default")
      (node (ref "U$14") (pin "UGND1") (pinfunction "UGND1_UGND1") (pintype "bidirectional"))
    )
    (net (code "140") (name "unconnected-(U$14-PadUGND2)") (class "Default")
      (node (ref "U$14") (pin "UGND2") (pinfunction "UGND2_UGND2") (pintype "bidirectional"))
    )
    (net (code "141") (name "unconnected-(U$14-PadVBAT)") (class "Default")
      (node (ref "U$14") (pin "VBAT") (pinfunction "VBAT_VBAT") (pintype "bidirectional"))
    )
    (net (code "142") (name "unconnected-(U$14-PadVUSB)") (class "Default")
      (node (ref "U$14") (pin "VUSB") (pinfunction "VUSB_VUSB") (pintype "bidirectional"))
    )
    (net (code "143") (name "unconnected-(U$15-DIO0-Pad20)") (class "Default")
      (node (ref "U$15") (pin "20") (pinfunction "DIO0_20") (pintype "bidirectional"))
    )
    (net (code "144") (name "unconnected-(U$15-DIO1-Pad19)") (class "Default")
      (node (ref "U$15") (pin "19") (pinfunction "DIO1_19") (pintype "bidirectional"))
    )
    (net (code "145") (name "unconnected-(U$15-DIO2-Pad18)") (class "Default")
      (node (ref "U$15") (pin "18") (pinfunction "DIO2_18") (pintype "bidirectional"))
    )
    (net (code "146") (name "unconnected-(U$15-DIO3-Pad17)") (class "Default")
      (node (ref "U$15") (pin "17") (pinfunction "DIO3_17") (pintype "bidirectional"))
    )
    (net (code "147") (name "unconnected-(U$15-DIO4-Pad11)") (class "Default")
      (node (ref "U$15") (pin "11") (pinfunction "DIO4_11") (pintype "bidirectional"))
    )
    (net (code "148") (name "unconnected-(U$15-DIO5-Pad15)") (class "Default")
      (node (ref "U$15") (pin "15") (pinfunction "DIO5_15") (pintype "bidirectional"))
    )
    (net (code "149") (name "unconnected-(U$15-DIO9-Pad13)") (class "Default")
      (node (ref "U$15") (pin "13") (pinfunction "DIO9_13") (pintype "bidirectional"))
    )
    (net (code "150") (name "unconnected-(U$15-DIO11-Pad7)") (class "Default")
      (node (ref "U$15") (pin "7") (pinfunction "DIO11_7") (pintype "bidirectional"))
    )
    (net (code "151") (name "unconnected-(U$15-DIO12-Pad4)") (class "Default")
      (node (ref "U$15") (pin "4") (pinfunction "DIO12_4") (pintype "bidirectional"))
    )
    (net (code "152") (name "unconnected-(U$15-DTR-Pad9)") (class "Default")
      (node (ref "U$15") (pin "9") (pinfunction "DTR_9") (pintype "bidirectional"))
    )
    (net (code "153") (name "unconnected-(U$15-RES-Pad8)") (class "Default")
      (node (ref "U$15") (pin "8") (pinfunction "RES_8") (pintype "bidirectional"))
    )
    (net (code "154") (name "unconnected-(U$15-RES-Pad14)") (class "Default")
      (node (ref "U$15") (pin "14") (pinfunction "RES_14") (pintype "bidirectional"))
    )
    (net (code "155") (name "unconnected-(U$15-RSSI-Pad6)") (class "Default")
      (node (ref "U$15") (pin "6") (pinfunction "RSSI_6") (pintype "bidirectional"))
    )
    (net (code "156") (name "unconnected-(U$16-CS_DIS-Pad6)") (class "Default")
      (node (ref "U$16") (pin "6") (pinfunction "CS_DIS_6") (pintype "bidirectional"))
    )
    (net (code "157") (name "unconnected-(U$17-GPA0-Pad21)") (class "Default")
      (node (ref "U$17") (pin "21") (pinfunction "GPA0_21") (pintype "bidirectional"))
    )
    (net (code "158") (name "unconnected-(U$17-GPA1-Pad22)") (class "Default")
      (node (ref "U$17") (pin "22") (pinfunction "GPA1_22") (pintype "bidirectional"))
    )
    (net (code "159") (name "unconnected-(U$17-GPA2-Pad23)") (class "Default")
      (node (ref "U$17") (pin "23") (pinfunction "GPA2_23") (pintype "bidirectional"))
    )
    (net (code "160") (name "unconnected-(U$17-GPA3-Pad24)") (class "Default")
      (node (ref "U$17") (pin "24") (pinfunction "GPA3_24") (pintype "bidirectional"))
    )
    (net (code "161") (name "unconnected-(U$17-GPB4-Pad5)") (class "Default")
      (node (ref "U$17") (pin "5") (pinfunction "GPB4_5") (pintype "bidirectional"))
    )
    (net (code "162") (name "unconnected-(U$17-GPB5-Pad6)") (class "Default")
      (node (ref "U$17") (pin "6") (pinfunction "GPB5_6") (pintype "bidirectional"))
    )
    (net (code "163") (name "unconnected-(U$17-GPB6-Pad7)") (class "Default")
      (node (ref "U$17") (pin "7") (pinfunction "GPB6_7") (pintype "bidirectional"))
    )
    (net (code "164") (name "unconnected-(U$17-GPB7-Pad8)") (class "Default")
      (node (ref "U$17") (pin "8") (pinfunction "GPB7_8") (pintype "bidirectional"))
    )
    (net (code "165") (name "unconnected-(U$17-INTB-Pad19)") (class "Default")
      (node (ref "U$17") (pin "19") (pinfunction "INTB_19") (pintype "bidirectional"))
    )
    (net (code "166") (name "unconnected-(U$17-NC0-Pad11)") (class "Default")
      (node (ref "U$17") (pin "11") (pinfunction "NC0_11") (pintype "bidirectional"))
    )
    (net (code "167") (name "unconnected-(U$17-NC1-Pad14)") (class "Default")
      (node (ref "U$17") (pin "14") (pinfunction "NC1_14") (pintype "bidirectional"))
    )
    (net (code "168") (name "unconnected-(U$21-GPA0-Pad21)") (class "Default")
      (node (ref "U$21") (pin "21") (pinfunction "GPA0_21") (pintype "bidirectional"))
    )
    (net (code "169") (name "unconnected-(U$21-GPA1-Pad22)") (class "Default")
      (node (ref "U$21") (pin "22") (pinfunction "GPA1_22") (pintype "bidirectional"))
    )
    (net (code "170") (name "unconnected-(U$21-GPA2-Pad23)") (class "Default")
      (node (ref "U$21") (pin "23") (pinfunction "GPA2_23") (pintype "bidirectional"))
    )
    (net (code "171") (name "unconnected-(U$21-GPA3-Pad24)") (class "Default")
      (node (ref "U$21") (pin "24") (pinfunction "GPA3_24") (pintype "bidirectional"))
    )
    (net (code "172") (name "unconnected-(U$21-GPB4-Pad5)") (class "Default")
      (node (ref "U$21") (pin "5") (pinfunction "GPB4_5") (pintype "bidirectional"))
    )
    (net (code "173") (name "unconnected-(U$21-GPB5-Pad6)") (class "Default")
      (node (ref "U$21") (pin "6") (pinfunction "GPB5_6") (pintype "bidirectional"))
    )
    (net (code "174") (name "unconnected-(U$21-GPB6-Pad7)") (class "Default")
      (node (ref "U$21") (pin "7") (pinfunction "GPB6_7") (pintype "bidirectional"))
    )
    (net (code "175") (name "unconnected-(U$21-GPB7-Pad8)") (class "Default")
      (node (ref "U$21") (pin "8") (pinfunction "GPB7_8") (pintype "bidirectional"))
    )
    (net (code "176") (name "unconnected-(U$21-INTB-Pad19)") (class "Default")
      (node (ref "U$21") (pin "19") (pinfunction "INTB_19") (pintype "bidirectional"))
    )
    (net (code "177") (name "unconnected-(U$21-NC0-Pad11)") (class "Default")
      (node (ref "U$21") (pin "11") (pinfunction "NC0_11") (pintype "bidirectional"))
    )
    (net (code "178") (name "unconnected-(U$21-NC1-Pad14)") (class "Default")
      (node (ref "U$21") (pin "14") (pinfunction "NC1_14") (pintype "bidirectional"))
    )
    (net (code "179") (name "unconnected-(U$23-CS_DIS-Pad6)") (class "Default")
      (node (ref "U$23") (pin "6") (pinfunction "CS_DIS_6") (pintype "bidirectional"))
    )
    (net (code "180") (name "unconnected-(U$25-CS_DIS-Pad6)") (class "Default")
      (node (ref "U$25") (pin "6") (pinfunction "CS_DIS_6") (pintype "bidirectional"))
    )
    (net (code "181") (name "unconnected-(U$27-CS_DIS-Pad6)") (class "Default")
      (node (ref "U$27") (pin "6") (pinfunction "CS_DIS_6") (pintype "bidirectional"))
    )
  )
)
